# design.net
KiCad netlist of a schematic drawn in Altium Designer
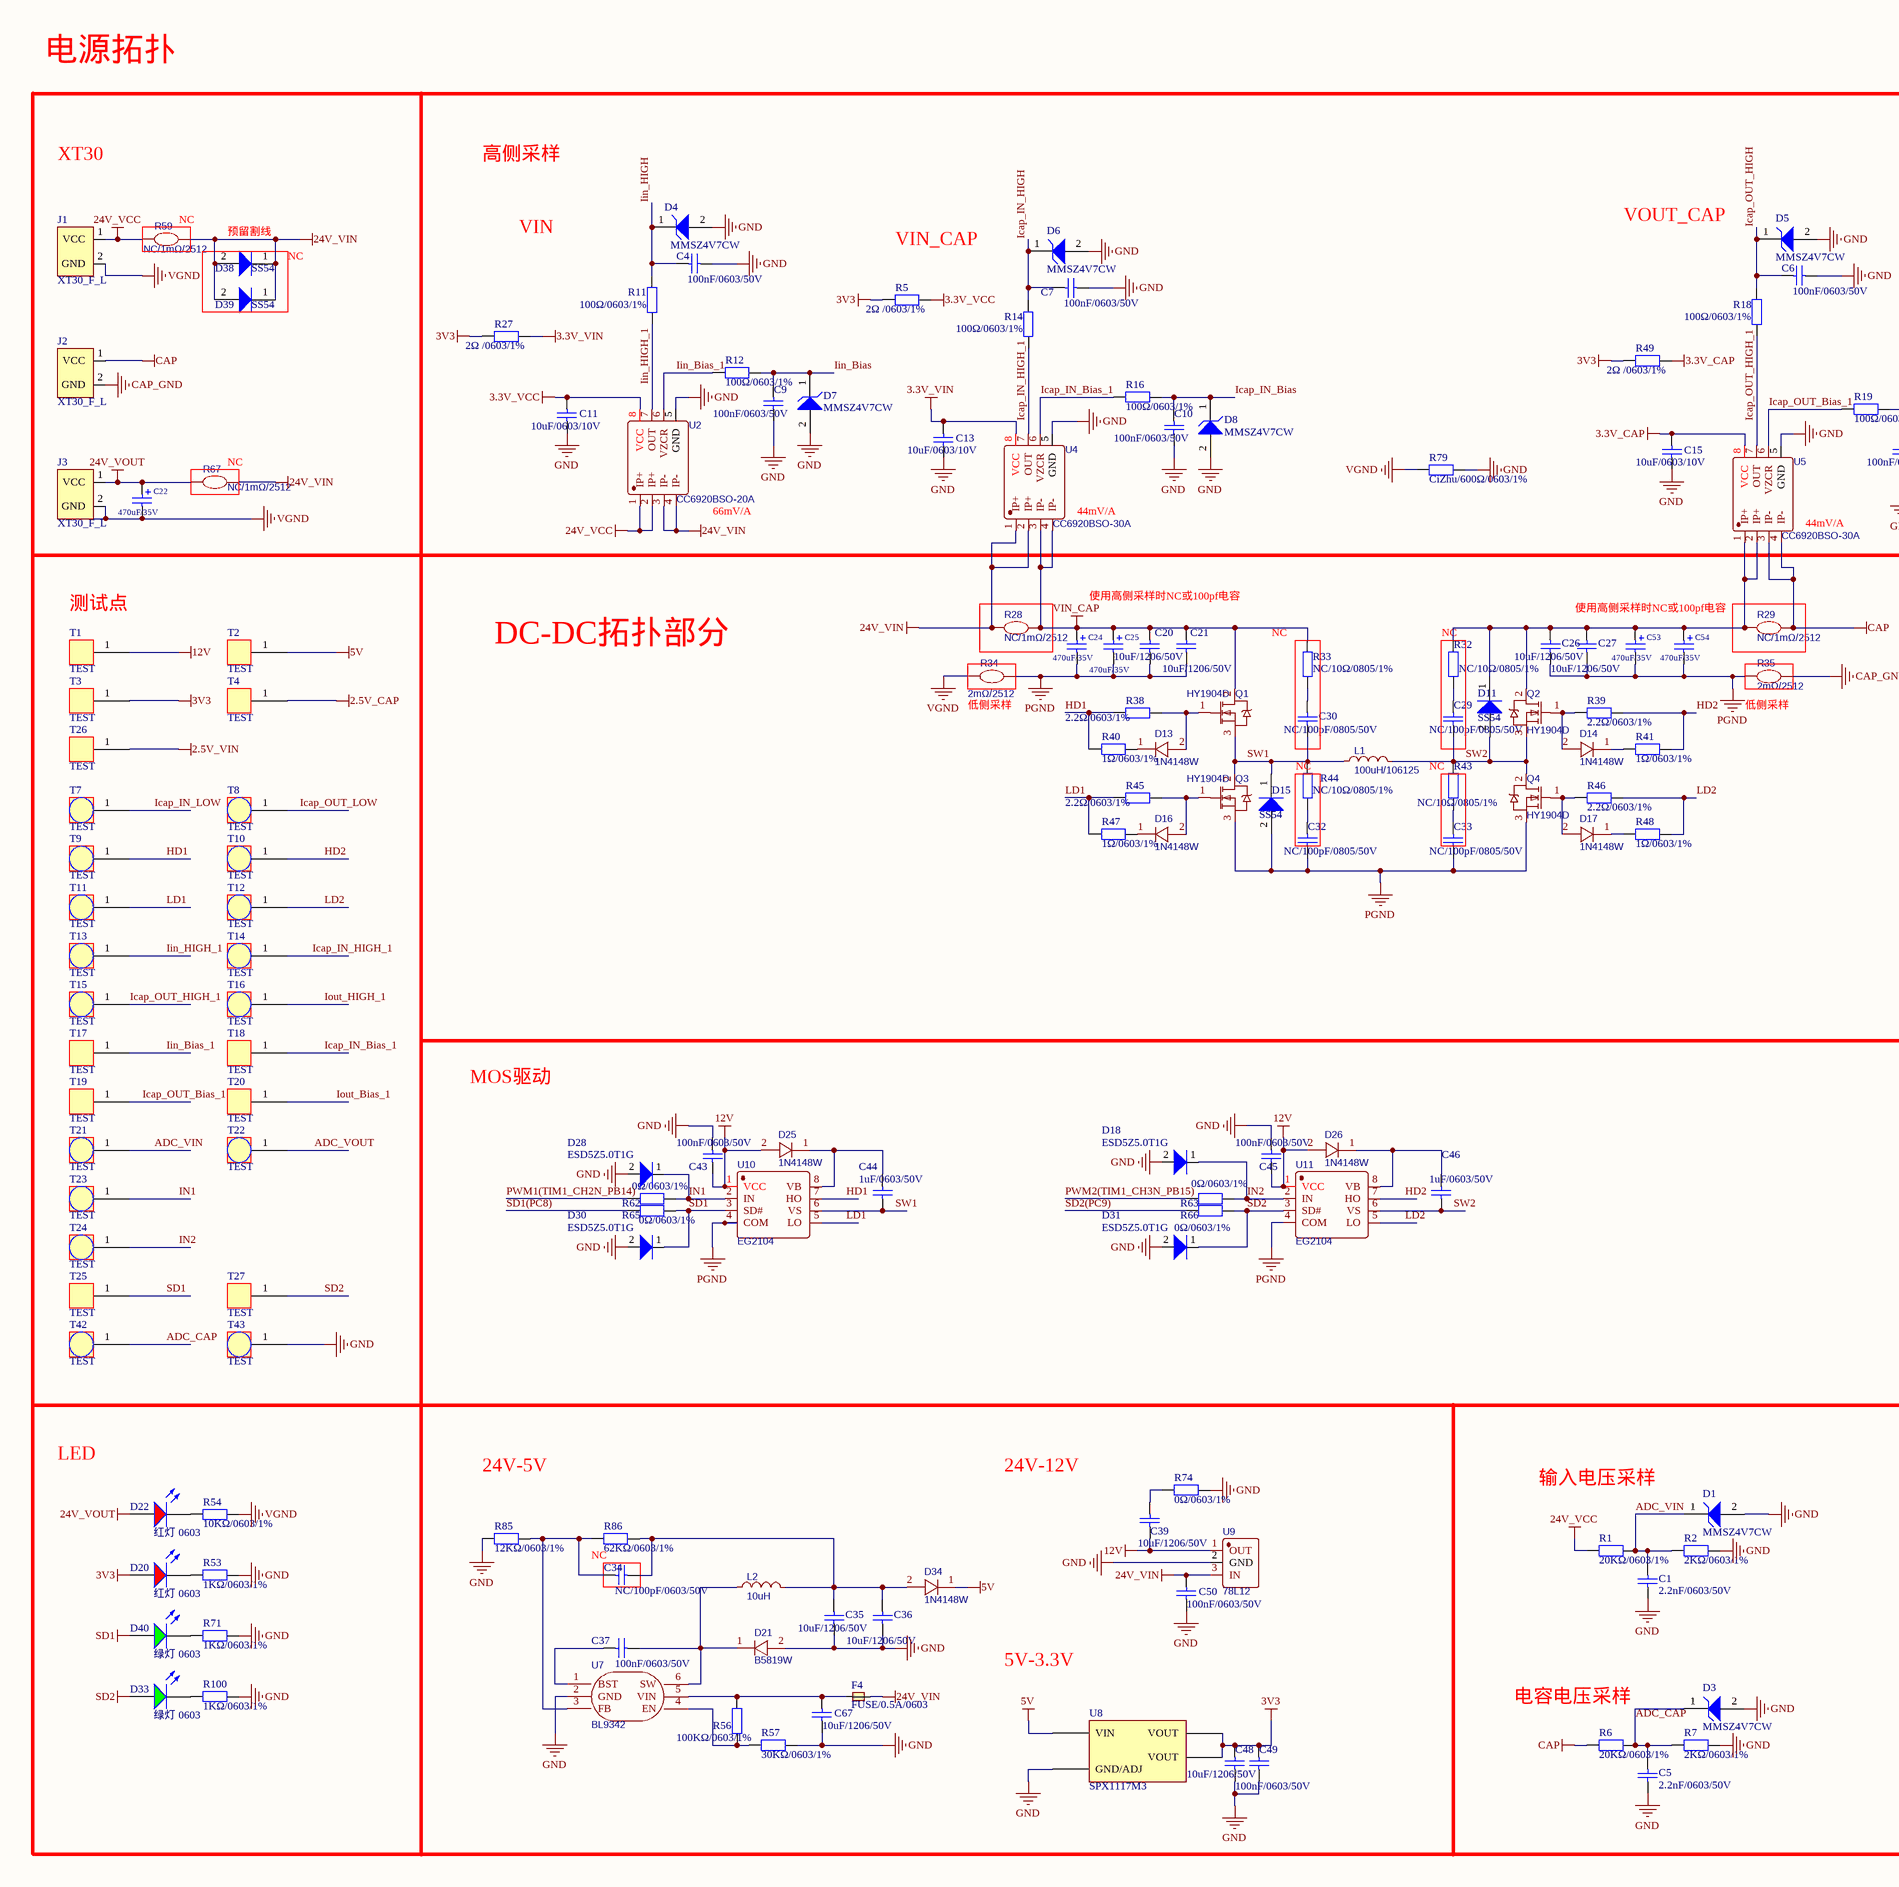
[diagram p0: 电源拓扑.SchDoc, left]
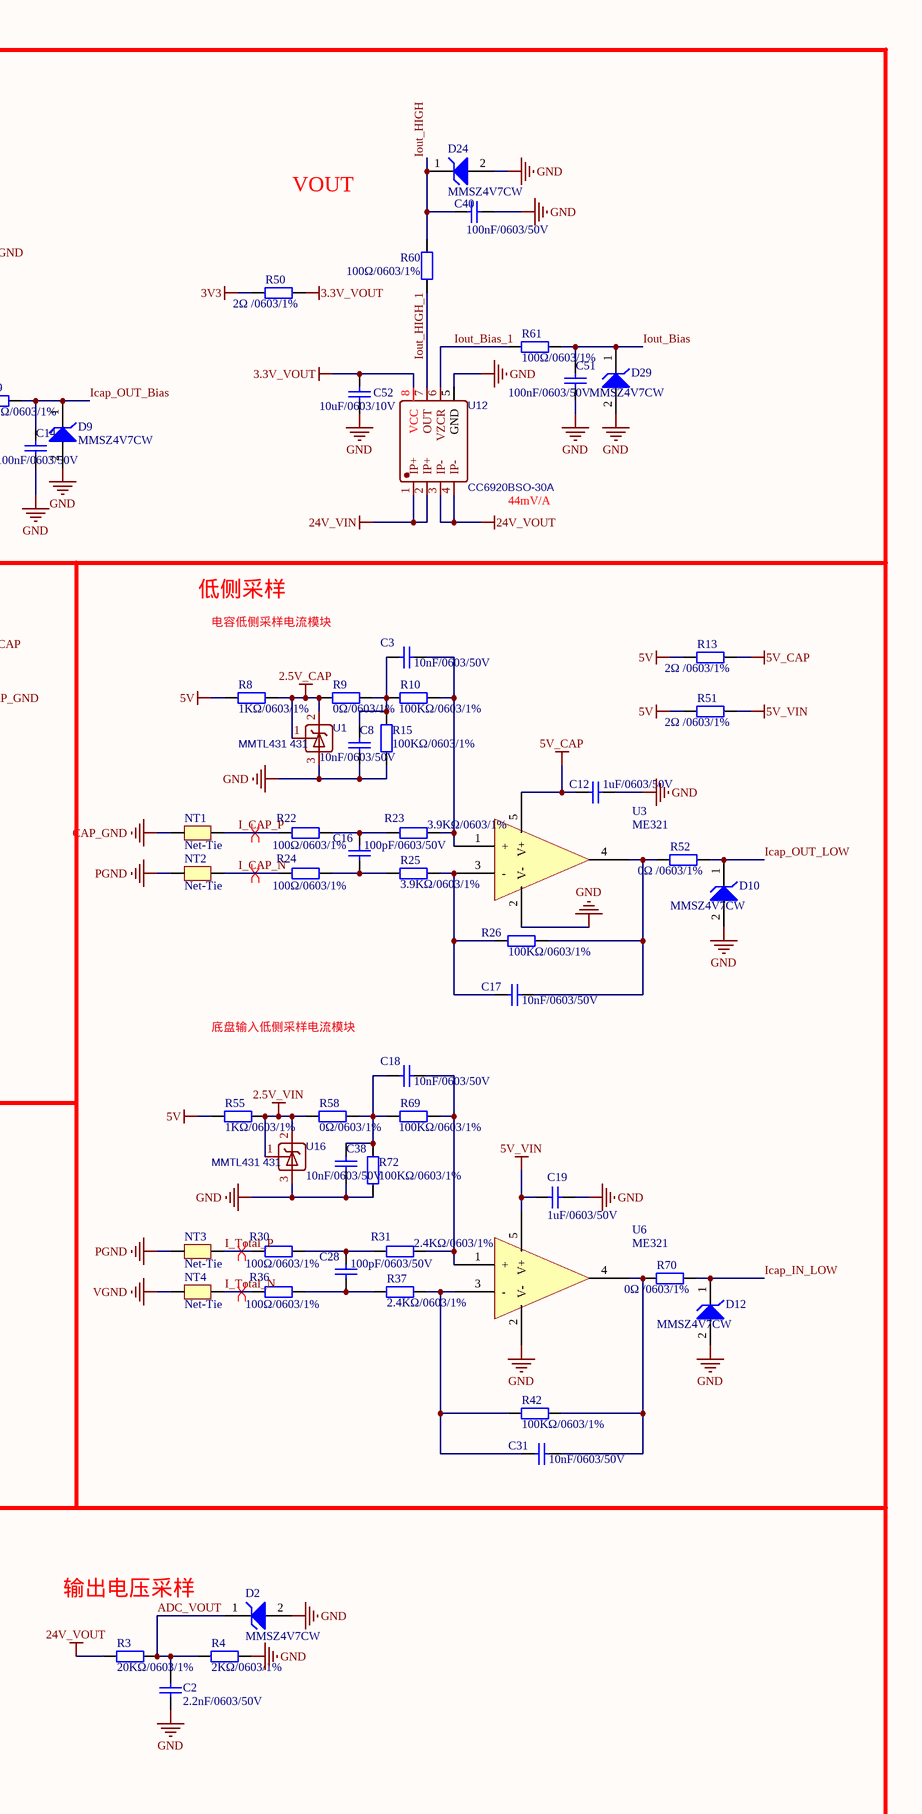
[diagram p1: 电源拓扑.SchDoc, right]

(export (version "E")
  (design (tool "Eeschema 10.0.6"))
  (components
    (comp (ref "C1")
      (value "2.2nF/0603/50V")
      (footprint "0603_C")
      (description "贴片电容")
      (libsource (lib "Miscellaneous Devices LC") (part "0603 100pF (101) 5% 50V"))
    )
    (comp (ref "C2")
      (value "2.2nF/0603/50V")
      (footprint "0603_C")
      (description "贴片电容")
      (libsource (lib "Miscellaneous Devices LC") (part "0603 100pF (101) 5% 50V"))
    )
    (comp (ref "C3")
      (value "10nF/0603/50V")
      (footprint "0603_C")
      (description "贴片电容")
      (libsource (lib "Miscellaneous Devices LC") (part "0603 100pF (101) 5% 50V"))
    )
    (comp (ref "C4")
      (value "100nF/0603/50V")
      (footprint "0603_C")
      (description "贴片电容")
      (libsource (lib "Miscellaneous Devices LC") (part "0603 100pF (101) 5% 50V"))
    )
    (comp (ref "C5")
      (value "2.2nF/0603/50V")
      (footprint "0603_C")
      (description "贴片电容")
      (libsource (lib "Miscellaneous Devices LC") (part "0603 100pF (101) 5% 50V"))
    )
    (comp (ref "C6")
      (value "100nF/0603/50V")
      (footprint "0603_C")
      (description "贴片电容")
      (libsource (lib "Miscellaneous Devices LC") (part "0603 100pF (101) 5% 50V"))
    )
    (comp (ref "C7")
      (value "100nF/0603/50V")
      (footprint "0603_C")
      (description "贴片电容")
      (libsource (lib "Miscellaneous Devices LC") (part "0603 100pF (101) 5% 50V"))
    )
    (comp (ref "C8")
      (value "10nF/0603/50V")
      (footprint "0603_C")
      (description "贴片电容")
      (libsource (lib "Miscellaneous Devices LC") (part "0603 100pF (101) 5% 50V"))
    )
    (comp (ref "C9")
      (value "100nF/0603/50V")
      (footprint "0603_C")
      (description "贴片电容")
      (libsource (lib "Miscellaneous Devices LC") (part "0603 100pF (101) 5% 50V"))
    )
    (comp (ref "C10")
      (value "100nF/0603/50V")
      (footprint "0603_C")
      (description "贴片电容")
      (libsource (lib "Miscellaneous Devices LC") (part "0603 100pF (101) 5% 50V"))
    )
    (comp (ref "C11")
      (value "10uF/0603/10V")
      (footprint "0603_C")
      (description "贴片电容")
      (libsource (lib "Miscellaneous Devices LC") (part "0603 10uF (106) 10% 10V"))
    )
    (comp (ref "C12")
      (value "1uF/0603/50V")
      (footprint "0603_C")
      (description "贴片电容")
      (libsource (lib "Miscellaneous Devices LC") (part "0603 100pF (101) 5% 50V"))
    )
    (comp (ref "C13")
      (value "10uF/0603/10V")
      (footprint "0603_C")
      (description "贴片电容")
      (libsource (lib "Miscellaneous Devices LC") (part "0603 10uF (106) 10% 10V"))
    )
    (comp (ref "C14")
      (value "100nF/0603/50V")
      (footprint "0603_C")
      (description "贴片电容")
      (libsource (lib "Miscellaneous Devices LC") (part "0603 100pF (101) 5% 50V"))
    )
    (comp (ref "C15")
      (value "10uF/0603/10V")
      (footprint "0603_C")
      (description "贴片电容")
      (libsource (lib "Miscellaneous Devices LC") (part "0603 10uF (106) 10% 10V"))
    )
    (comp (ref "C16")
      (value "100pF/0603/50V")
      (footprint "0603_C")
      (description "贴片电容")
      (libsource (lib "Miscellaneous Devices LC") (part "0603 100pF (101) 5% 50V"))
    )
    (comp (ref "C17")
      (value "10nF/0603/50V")
      (footprint "0603_C")
      (description "贴片电容")
      (libsource (lib "Miscellaneous Devices LC") (part "0603 100pF (101) 5% 50V"))
    )
    (comp (ref "C18")
      (value "10nF/0603/50V")
      (footprint "0603_C")
      (description "贴片电容")
      (libsource (lib "Miscellaneous Devices LC") (part "0603 100pF (101) 5% 50V"))
    )
    (comp (ref "C19")
      (value "1uF/0603/50V")
      (footprint "0603_C")
      (description "贴片电容")
      (libsource (lib "Miscellaneous Devices LC") (part "0603 10uF (106) 10% 10V"))
    )
    (comp (ref "C20")
      (value "10uF/1206/50V")
      (footprint "1206_C")
      (description "贴片电容")
      (libsource (lib "Miscellaneous Devices LC") (part "1206 10uF (106) 10% 50V"))
    )
    (comp (ref "C21")
      (value "10uF/1206/50V")
      (footprint "1206_C")
      (description "贴片电容")
      (libsource (lib "Miscellaneous Devices LC") (part "1206 10uF (106) 10% 50V"))
    )
    (comp (ref "C22")
      (value "470uF/35V")
      (footprint "CAP_10x16mm")
      (description "铝电解电容")
      (libsource (lib "数字电源") (part "CAP_470uF/35V/10x16mm"))
    )
    (comp (ref "C24")
      (value "470uF/35V")
      (footprint "CAP_10x16mm")
      (description "铝电解电容")
      (libsource (lib "数字电源") (part "CAP_470uF/35V/10x16mm"))
    )
    (comp (ref "C25")
      (value "470uF/35V")
      (footprint "CAP_10x16mm")
      (description "铝电解电容")
      (libsource (lib "数字电源") (part "CAP_470uF/35V/10x16mm"))
    )
    (comp (ref "C26")
      (value "10uF/1206/50V")
      (footprint "1206_C")
      (description "贴片电容")
      (libsource (lib "Miscellaneous Devices LC") (part "1206 10uF (106) 10% 50V"))
    )
    (comp (ref "C27")
      (value "10uF/1206/50V")
      (footprint "1206_C")
      (description "贴片电容")
      (libsource (lib "Miscellaneous Devices LC") (part "1206 10uF (106) 10% 50V"))
    )
    (comp (ref "C28")
      (value "100pF/0603/50V")
      (footprint "0603_C")
      (description "贴片电容")
      (libsource (lib "Miscellaneous Devices LC") (part "0603 100pF (101) 5% 50V"))
    )
    (comp (ref "C29")
      (value "NC/100pF/0805/50V")
      (footprint "0805_C")
      (description "贴片电容")
      (libsource (lib "Miscellaneous Devices LC") (part "0805 100pF (101) 5% 50V"))
    )
    (comp (ref "C30")
      (value "NC/100pF/0805/50V")
      (footprint "0805_C")
      (description "贴片电容")
      (libsource (lib "Miscellaneous Devices LC") (part "0805 100pF (101) 5% 50V"))
    )
    (comp (ref "C31")
      (value "10nF/0603/50V")
      (footprint "0603_C")
      (description "贴片电容")
      (libsource (lib "Miscellaneous Devices LC") (part "0603 100pF (101) 5% 50V"))
    )
    (comp (ref "C32")
      (value "NC/100pF/0805/50V")
      (footprint "0805_C")
      (description "贴片电容")
      (libsource (lib "Miscellaneous Devices LC") (part "0805 100pF (101) 5% 50V"))
    )
    (comp (ref "C33")
      (value "NC/100pF/0805/50V")
      (footprint "0805_C")
      (description "贴片电容")
      (libsource (lib "Miscellaneous Devices LC") (part "0805 100pF (101) 5% 50V"))
    )
    (comp (ref "C34")
      (value "NC/100pF/0603/50V")
      (footprint "0603_C")
      (description "贴片电容")
      (libsource (lib "Miscellaneous Devices LC") (part "0603 100pF (101) 5% 50V"))
    )
    (comp (ref "C35")
      (value "10uF/1206/50V")
      (footprint "1206_C")
      (description "贴片电容")
      (libsource (lib "Miscellaneous Devices LC") (part "1206 10uF (106) 10% 50V"))
    )
    (comp (ref "C36")
      (value "10uF/1206/50V")
      (footprint "1206_C")
      (description "贴片电容")
      (libsource (lib "Miscellaneous Devices LC") (part "1206 10uF (106) 10% 50V"))
    )
    (comp (ref "C37")
      (value "100nF/0603/50V")
      (footprint "0603_C")
      (description "贴片电容")
      (libsource (lib "Miscellaneous Devices LC") (part "0603 100pF (101) 5% 50V"))
    )
    (comp (ref "C38")
      (value "10nF/0603/50V")
      (footprint "0603_C")
      (description "贴片电容")
      (libsource (lib "Miscellaneous Devices LC") (part "0603 100pF (101) 5% 50V"))
    )
    (comp (ref "C39")
      (value "10uF/1206/50V")
      (footprint "1206_C")
      (description "贴片电容")
      (libsource (lib "Miscellaneous Devices LC") (part "1206 10uF (106) 10% 50V"))
    )
    (comp (ref "C40")
      (value "100nF/0603/50V")
      (footprint "0603_C")
      (description "贴片电容")
      (libsource (lib "Miscellaneous Devices LC") (part "0603 100pF (101) 5% 50V"))
    )
    (comp (ref "C43")
      (value "100nF/0603/50V")
      (footprint "0603_C")
      (description "贴片电容")
      (libsource (lib "Miscellaneous Devices LC") (part "0603 100pF (101) 5% 50V"))
    )
    (comp (ref "C44")
      (value "1uF/0603/50V")
      (footprint "0603_C")
      (description "贴片电容")
      (libsource (lib "Miscellaneous Devices LC") (part "0603 100pF (101) 5% 50V"))
    )
    (comp (ref "C45")
      (value "100nF/0603/50V")
      (footprint "0603_C")
      (description "贴片电容")
      (libsource (lib "Miscellaneous Devices LC") (part "0603 100pF (101) 5% 50V"))
    )
    (comp (ref "C46")
      (value "1uF/0603/50V")
      (footprint "0603_C")
      (description "贴片电容")
      (libsource (lib "Miscellaneous Devices LC") (part "0603 100pF (101) 5% 50V"))
    )
    (comp (ref "C48")
      (value "100nF/0603/50V")
      (footprint "0603_C")
      (description "贴片电容")
      (libsource (lib "Miscellaneous Devices LC") (part "0603 100pF (101) 5% 50V"))
    )
    (comp (ref "C49")
      (value "10uF/1206/50V")
      (footprint "1206_C")
      (description "贴片电容")
      (libsource (lib "Miscellaneous Devices LC") (part "1206 10uF (106) 10% 50V"))
    )
    (comp (ref "C50")
      (value "100nF/0603/50V")
      (footprint "0603_C")
      (description "贴片电容")
      (libsource (lib "Miscellaneous Devices LC") (part "0603 100pF (101) 5% 50V"))
    )
    (comp (ref "C51")
      (value "100nF/0603/50V")
      (footprint "0603_C")
      (description "贴片电容")
      (libsource (lib "Miscellaneous Devices LC") (part "0603 100pF (101) 5% 50V"))
    )
    (comp (ref "C52")
      (value "10uF/0603/10V")
      (footprint "0603_C")
      (description "贴片电容")
      (libsource (lib "Miscellaneous Devices LC") (part "0603 10uF (106) 10% 10V"))
    )
    (comp (ref "C53")
      (value "470uF/35V")
      (footprint "CAP_10x16mm")
      (description "铝电解电容")
      (libsource (lib "数字电源") (part "CAP_470uF/35V/10x16mm"))
    )
    (comp (ref "C54")
      (value "470uF/35V")
      (footprint "CAP_10x16mm")
      (description "铝电解电容")
      (libsource (lib "数字电源") (part "CAP_470uF/35V/10x16mm"))
    )
    (comp (ref "C67")
      (value "10uF/1206/50V")
      (footprint "1206_C")
      (description "贴片电容")
      (libsource (lib "Miscellaneous Devices LC") (part "1206 10uF (106) 10% 50V"))
    )
    (comp (ref "D1")
      (value "MMSZ4V7CW")
      (footprint "SOD-123")
      (description "稳压二极管")
      (libsource (lib "数字电源") (part "LL-34 ZMM3V3"))
    )
    (comp (ref "D2")
      (value "MMSZ4V7CW")
      (footprint "SOD-123")
      (description "稳压二极管")
      (libsource (lib "数字电源") (part "LL-34 ZMM3V3"))
    )
    (comp (ref "D3")
      (value "MMSZ4V7CW")
      (footprint "SOD-123")
      (description "稳压二极管")
      (libsource (lib "数字电源") (part "LL-34 ZMM3V3"))
    )
    (comp (ref "D4")
      (value "MMSZ4V7CW")
      (footprint "SOD-123")
      (description "稳压二极管")
      (libsource (lib "数字电源") (part "LL-34 ZMM3V3"))
    )
    (comp (ref "D5")
      (value "MMSZ4V7CW")
      (footprint "SOD-123")
      (description "稳压二极管")
      (libsource (lib "数字电源") (part "LL-34 ZMM3V3"))
    )
    (comp (ref "D6")
      (value "MMSZ4V7CW")
      (footprint "SOD-123")
      (description "稳压二极管")
      (libsource (lib "数字电源") (part "LL-34 ZMM3V3"))
    )
    (comp (ref "D7")
      (value "MMSZ4V7CW")
      (footprint "SOD-123")
      (description "稳压二极管")
      (libsource (lib "数字电源") (part "LL-34 ZMM3V3"))
    )
    (comp (ref "D8")
      (value "MMSZ4V7CW")
      (footprint "SOD-123")
      (description "稳压二极管")
      (libsource (lib "数字电源") (part "LL-34 ZMM3V3"))
    )
    (comp (ref "D9")
      (value "MMSZ4V7CW")
      (footprint "SOD-123")
      (description "稳压二极管")
      (libsource (lib "数字电源") (part "LL-34 ZMM3V3"))
    )
    (comp (ref "D10")
      (value "MMSZ4V7CW")
      (footprint "SOD-123")
      (description "稳压二极管")
      (libsource (lib "数字电源") (part "LL-34 ZMM3V3"))
    )
    (comp (ref "D11")
      (value "SS54")
      (footprint "SMA")
      (description "二极管")
      (libsource (lib "数字电源") (part "SS54"))
    )
    (comp (ref "D12")
      (value "MMSZ4V7CW")
      (footprint "SOD-123")
      (description "稳压二极管")
      (libsource (lib "数字电源") (part "LL-34 ZMM3V3"))
    )
    (comp (ref "D13")
      (value "1N4148W")
      (footprint "SOD-123_L2.7-W1.6-LS3.7-RD")
      (description "开关二极管")
      (fields (field (name "BOM_SUPPLIER PART") "C466653") (field (name "CONTRIBUTOR") "LCSC"))
      (libsource (lib "数字电源") (part "1N4148W"))
    )
    (comp (ref "D14")
      (value "1N4148W")
      (footprint "SOD-123_L2.7-W1.6-LS3.7-RD")
      (description "开关二极管")
      (fields (field (name "BOM_SUPPLIER PART") "C466653") (field (name "CONTRIBUTOR") "LCSC"))
      (libsource (lib "数字电源") (part "1N4148W"))
    )
    (comp (ref "D15")
      (value "SS54")
      (footprint "SMA")
      (description "二极管")
      (libsource (lib "数字电源") (part "SS54"))
    )
    (comp (ref "D16")
      (value "1N4148W")
      (footprint "SOD-123_L2.7-W1.6-LS3.7-RD")
      (description "开关二极管")
      (fields (field (name "BOM_SUPPLIER PART") "C466653") (field (name "CONTRIBUTOR") "LCSC"))
      (libsource (lib "数字电源") (part "1N4148W"))
    )
    (comp (ref "D17")
      (value "1N4148W")
      (footprint "SOD-123_L2.7-W1.6-LS3.7-RD")
      (description "开关二极管")
      (fields (field (name "BOM_SUPPLIER PART") "C466653") (field (name "CONTRIBUTOR") "LCSC"))
      (libsource (lib "数字电源") (part "1N4148W"))
    )
    (comp (ref "D18")
      (value "ESD5Z5.0T1G")
      (footprint "SOD-523")
      (description "单向TVS")
      (libsource (lib "数字电源") (part "TVS_SOD-523"))
    )
    (comp (ref "D20")
      (value "红灯 0603")
      (footprint "0603_LED_S1")
      (description "发光二极管")
      (libsource (lib "Miscellaneous Devices LC") (part "0603 红灯"))
    )
    (comp (ref "D21")
      (value "B5819W")
      (footprint "SOD-123_L2.7-W1.6-LS3.7-RD")
      (description "开关二极管")
      (fields
        (field (name "BOM_SUPPLIER PART") "C466653")
        (field (name "BOM_MANUFACTURER PART") "1N4148W")
        (field (name "CONTRIBUTOR") "LCSC")
      )
      (libsource (lib "数字电源") (part "1N4148W"))
    )
    (comp (ref "D22")
      (value "红灯 0603")
      (footprint "0603_LED_S1")
      (description "发光二极管")
      (libsource (lib "Miscellaneous Devices LC") (part "0603 红灯"))
    )
    (comp (ref "D24")
      (value "MMSZ4V7CW")
      (footprint "SOD-123")
      (description "稳压二极管")
      (libsource (lib "数字电源") (part "LL-34 ZMM3V3"))
    )
    (comp (ref "D25")
      (value "1N4148W")
      (footprint "SOD-123_L2.7-W1.6-LS3.7-RD")
      (description "开关二极管")
      (fields (field (name "BOM_SUPPLIER PART") "C466653") (field (name "CONTRIBUTOR") "LCSC"))
      (libsource (lib "数字电源") (part "1N4148W"))
    )
    (comp (ref "D26")
      (value "1N4148W")
      (footprint "SOD-123_L2.7-W1.6-LS3.7-RD")
      (description "开关二极管")
      (fields (field (name "BOM_SUPPLIER PART") "C466653") (field (name "CONTRIBUTOR") "LCSC"))
      (libsource (lib "数字电源") (part "1N4148W"))
    )
    (comp (ref "D28")
      (value "ESD5Z5.0T1G")
      (footprint "SOD-523")
      (description "单向TVS")
      (libsource (lib "数字电源") (part "TVS_SOD-523"))
    )
    (comp (ref "D29")
      (value "MMSZ4V7CW")
      (footprint "SOD-123")
      (description "稳压二极管")
      (libsource (lib "数字电源") (part "LL-34 ZMM3V3"))
    )
    (comp (ref "D30")
      (value "ESD5Z5.0T1G")
      (footprint "SOD-523")
      (description "单向TVS")
      (libsource (lib "数字电源") (part "TVS_SOD-523"))
    )
    (comp (ref "D31")
      (value "ESD5Z5.0T1G")
      (footprint "SOD-523")
      (description "单向TVS")
      (libsource (lib "数字电源") (part "TVS_SOD-523"))
    )
    (comp (ref "D33")
      (value "绿灯 0603")
      (footprint "0603_LED_S1")
      (description "发光二极管")
      (libsource (lib "Miscellaneous Devices LC") (part "0603 绿灯"))
    )
    (comp (ref "D34")
      (value "1N4148W")
      (footprint "SOD-123_L2.7-W1.6-LS3.7-RD")
      (description "开关二极管")
      (fields (field (name "BOM_SUPPLIER PART") "C466653") (field (name "CONTRIBUTOR") "LCSC"))
      (libsource (lib "数字电源") (part "1N4148W"))
    )
    (comp (ref "D38")
      (value "SS54")
      (footprint "SMA")
      (description "二极管")
      (libsource (lib "数字电源") (part "SS54"))
    )
    (comp (ref "D39")
      (value "SS54")
      (footprint "SMA")
      (description "二极管")
      (libsource (lib "数字电源") (part "SS54"))
    )
    (comp (ref "D40")
      (value "绿灯 0603")
      (footprint "0603_LED_S1")
      (description "发光二极管")
      (libsource (lib "Miscellaneous Devices LC") (part "0603 绿灯"))
    )
    (comp (ref "F4")
      (value "FUSE/0.5A/0603")
      (footprint "0.5A/0603")
      (description "FUSE")
      (libsource (lib "数字电源") (part "FUSE/0.5A/0603"))
    )
    (comp (ref "J1")
      (value "XT30_F_L")
      (footprint "RobotLab_Common_Used:XT30内嵌无极性标识_F")
      (description "卧式XT30")
      (libsource (lib "RobotLab_Common_Used") (part "XT30_F_L"))
    )
    (comp (ref "J2")
      (value "XT30_F_L")
      (footprint "RobotLab_Common_Used:XT30内嵌无极性标识_F")
      (description "卧式XT30")
      (libsource (lib "RobotLab_Common_Used") (part "XT30_F_L"))
    )
    (comp (ref "J3")
      (value "XT30_F_L")
      (footprint "RobotLab_Common_Used:XT30内嵌无极性标识_F")
      (description "卧式XT30")
      (libsource (lib "RobotLab_Common_Used") (part "XT30_F_L"))
    )
    (comp (ref "L1")
      (value "100uH/106125")
      (footprint "106125")
      (description "磁环电感")
      (fields
        (field (name "BOM_SUPPLIER PART") "C497913")
        (field (name "BOM_MANUFACTURER PART") "YSPI1365-470M")
        (field (name "CONTRIBUTOR") "LCSC")
      )
      (libsource (lib "数字电源") (part "106125 卧式"))
    )
    (comp (ref "L2")
      (value "10uH")
      (footprint "IND-SMD_L5.0-W5.0-1")
      (description "功率电感")
      (fields
        (field (name "BOM_SUPPLIER PART") "C497913")
        (field (name "BOM_MANUFACTURER PART") "YSPI1365-470M")
        (field (name "CONTRIBUTOR") "LCSC")
      )
      (libsource (lib "数字电源") (part "15uH"))
    )
    (comp (ref "NT1") (value "Net-Tie") (footprint "Net_Tie_10mil") (libsource (lib "数字电源") (part "Net-Tie")))
    (comp (ref "NT2") (value "Net-Tie") (footprint "Net_Tie_10mil") (libsource (lib "数字电源") (part "Net-Tie")))
    (comp (ref "NT3") (value "Net-Tie") (footprint "Net_Tie_10mil") (libsource (lib "数字电源") (part "Net-Tie")))
    (comp (ref "NT4") (value "Net-Tie") (footprint "Net_Tie_10mil") (libsource (lib "数字电源") (part "Net-Tie")))
    (comp (ref "Q1")
      (value "HY1904D")
      (footprint "TO-252-2_L6.6-W6.1-P4.57-LS9.9-TL-CW")
      (fields (field (name "BOM_SUPPLIER PART") "C122488"))
      (libsource (lib "数字电源") (part "HY1904D"))
    )
    (comp (ref "Q2")
      (value "HY1904D")
      (footprint "TO-252-2_L6.6-W6.1-P4.57-LS9.9-TL-CW")
      (fields (field (name "BOM_SUPPLIER PART") "C122488"))
      (libsource (lib "数字电源") (part "HY1904D"))
    )
    (comp (ref "Q3")
      (value "HY1904D")
      (footprint "TO-252-2_L6.6-W6.1-P4.57-LS9.9-TL-CW")
      (fields (field (name "BOM_SUPPLIER PART") "C122488"))
      (libsource (lib "数字电源") (part "HY1904D"))
    )
    (comp (ref "Q4")
      (value "HY1904D")
      (footprint "TO-252-2_L6.6-W6.1-P4.57-LS9.9-TL-CW")
      (fields (field (name "BOM_SUPPLIER PART") "C122488"))
      (libsource (lib "数字电源") (part "HY1904D"))
    )
    (comp (ref "R1")
      (value "20KΩ/0603/1%")
      (footprint "0603_R")
      (description "贴片电阻")
      (libsource (lib "Miscellaneous Devices LC") (part "0603 10KΩ (1002) 1%"))
    )
    (comp (ref "R2")
      (value "2KΩ/0603/1%")
      (footprint "0603_R")
      (description "贴片电阻")
      (libsource (lib "Miscellaneous Devices LC") (part "0603 10KΩ (1002) 1%"))
    )
    (comp (ref "R3")
      (value "20KΩ/0603/1%")
      (footprint "0603_R")
      (description "贴片电阻")
      (libsource (lib "Miscellaneous Devices LC") (part "0603 10KΩ (1002) 1%"))
    )
    (comp (ref "R4")
      (value "2KΩ/0603/1%")
      (footprint "0603_R")
      (description "贴片电阻")
      (libsource (lib "Miscellaneous Devices LC") (part "0603 10KΩ (1002) 1%"))
    )
    (comp (ref "R5")
      (value "2Ω /0603/1%")
      (footprint "0603_R")
      (description "贴片电阻")
      (libsource (lib "Miscellaneous Devices LC") (part "0603 2.2Ω (2R20) 1%"))
    )
    (comp (ref "R6")
      (value "20KΩ/0603/1%")
      (footprint "0603_R")
      (description "贴片电阻")
      (libsource (lib "Miscellaneous Devices LC") (part "0603 10KΩ (1002) 1%"))
    )
    (comp (ref "R7")
      (value "2KΩ/0603/1%")
      (footprint "0603_R")
      (description "贴片电阻")
      (libsource (lib "Miscellaneous Devices LC") (part "0603 10KΩ (1002) 1%"))
    )
    (comp (ref "R8")
      (value "1KΩ/0603/1%")
      (footprint "0603_R")
      (description "贴片电阻")
      (libsource (lib "Miscellaneous Devices LC") (part "0603 10KΩ (1002) 1%"))
    )
    (comp (ref "R9")
      (value "0Ω/0603/1%")
      (footprint "0603_R")
      (description "贴片电阻")
      (libsource (lib "Miscellaneous Devices LC") (part "0603 0Ω (0R0) 1%"))
    )
    (comp (ref "R10")
      (value "100KΩ/0603/1%")
      (footprint "0603_R")
      (description "贴片电阻")
      (libsource (lib "Miscellaneous Devices LC") (part "0603 10KΩ (1002) 1%"))
    )
    (comp (ref "R11")
      (value "100Ω/0603/1%")
      (footprint "0603_R")
      (description "贴片电阻")
      (libsource (lib "Miscellaneous Devices LC") (part "0603 100Ω (1000) 1%"))
    )
    (comp (ref "R12")
      (value "100Ω/0603/1%")
      (footprint "0603_R")
      (description "贴片电阻")
      (libsource (lib "") (part "0603 100Ω (1000) 1%_2"))
    )
    (comp (ref "R13")
      (value "2Ω /0603/1%")
      (footprint "0603_R")
      (description "贴片电阻")
      (libsource (lib "Miscellaneous Devices LC") (part "0603 2.2Ω (2R20) 1%"))
    )
    (comp (ref "R14")
      (value "100Ω/0603/1%")
      (footprint "0603_R")
      (description "贴片电阻")
      (libsource (lib "Miscellaneous Devices LC") (part "0603 100Ω (1000) 1%"))
    )
    (comp (ref "R15")
      (value "100KΩ/0603/1%")
      (footprint "0603_R")
      (description "贴片电阻")
      (libsource (lib "") (part "0603 10KΩ (1002) 1%_1"))
    )
    (comp (ref "R16")
      (value "100Ω/0603/1%")
      (footprint "0603_R")
      (description "贴片电阻")
      (libsource (lib "") (part "0603 100Ω (1000) 1%_2"))
    )
    (comp (ref "R18")
      (value "100Ω/0603/1%")
      (footprint "0603_R")
      (description "贴片电阻")
      (libsource (lib "Miscellaneous Devices LC") (part "0603 100Ω (1000) 1%"))
    )
    (comp (ref "R19")
      (value "100Ω/0603/1%")
      (footprint "0603_R")
      (description "贴片电阻")
      (libsource (lib "") (part "0603 100Ω (1000) 1%_2"))
    )
    (comp (ref "R22")
      (value "100Ω/0603/1%")
      (footprint "0603_R")
      (description "贴片电阻")
      (libsource (lib "") (part "0603 100Ω (1000) 1%_1"))
    )
    (comp (ref "R23")
      (value "3.9KΩ/0603/1%")
      (footprint "0603_R")
      (description "贴片电阻")
      (libsource (lib "Miscellaneous Devices LC") (part "0603 3.9KΩ (3901) 1%"))
    )
    (comp (ref "R24")
      (value "100Ω/0603/1%")
      (footprint "0603_R")
      (description "贴片电阻")
      (libsource (lib "") (part "0603 100Ω (1000) 1%_1"))
    )
    (comp (ref "R25")
      (value "3.9KΩ/0603/1%")
      (footprint "0603_R")
      (description "贴片电阻")
      (libsource (lib "Miscellaneous Devices LC") (part "0603 3.9KΩ (3901) 1%"))
    )
    (comp (ref "R26")
      (value "100KΩ/0603/1%")
      (footprint "0603_R")
      (description "贴片电阻")
      (libsource (lib "Miscellaneous Devices LC") (part "0603 200KΩ (2003) 1%"))
    )
    (comp (ref "R27")
      (value "2Ω /0603/1%")
      (footprint "0603_R")
      (description "贴片电阻")
      (libsource (lib "Miscellaneous Devices LC") (part "0603 2.2Ω (2R20) 1%"))
    )
    (comp (ref "R28")
      (value "NC/1mΩ/2512")
      (footprint "R2512")
      (description "2512采样")
      (fields
        (field (name "BOM_SUPPLIER PART") "C393070")
        (field (name "BOM_MANUFACTURER PART") "RLP25FEGR010")
        (field (name "CONTRIBUTOR") "LCSC")
      )
      (libsource (lib "数字电源") (part "0.01"))
    )
    (comp (ref "R29")
      (value "NC/1mΩ/2512")
      (footprint "R2512")
      (description "2512采样")
      (fields
        (field (name "BOM_SUPPLIER PART") "C393070")
        (field (name "BOM_MANUFACTURER PART") "RLP25FEGR010")
        (field (name "CONTRIBUTOR") "LCSC")
      )
      (libsource (lib "数字电源") (part "0.01"))
    )
    (comp (ref "R30")
      (value "100Ω/0603/1%")
      (footprint "0603_R")
      (description "贴片电阻")
      (libsource (lib "") (part "0603 100Ω (1000) 1%_1"))
    )
    (comp (ref "R31")
      (value "2.4KΩ/0603/1%")
      (footprint "0603_R")
      (description "贴片电阻")
      (libsource (lib "Miscellaneous Devices LC") (part "0603 3.9KΩ (3901) 1%"))
    )
    (comp (ref "R32")
      (value "NC/10Ω/0805/1%")
      (footprint "0805_R")
      (description "贴片电阻")
      (libsource (lib "Miscellaneous Devices LC") (part "0805 10Ω (10R0) 1%"))
    )
    (comp (ref "R33")
      (value "NC/10Ω/0805/1%")
      (footprint "0805_R")
      (description "贴片电阻")
      (libsource (lib "Miscellaneous Devices LC") (part "0805 10Ω (10R0) 1%"))
    )
    (comp (ref "R34")
      (value "2mΩ/2512")
      (footprint "R2512")
      (description "2512采样")
      (fields
        (field (name "BOM_SUPPLIER PART") "C393070")
        (field (name "BOM_MANUFACTURER PART") "RLP25FEGR010")
        (field (name "CONTRIBUTOR") "LCSC")
      )
      (libsource (lib "数字电源") (part "0.01"))
    )
    (comp (ref "R35")
      (value "2mΩ/2512")
      (footprint "R2512")
      (description "2512采样")
      (fields
        (field (name "BOM_SUPPLIER PART") "C393070")
        (field (name "BOM_MANUFACTURER PART") "RLP25FEGR010")
        (field (name "CONTRIBUTOR") "LCSC")
      )
      (libsource (lib "数字电源") (part "0.01"))
    )
    (comp (ref "R36")
      (value "100Ω/0603/1%")
      (footprint "0603_R")
      (description "贴片电阻")
      (libsource (lib "") (part "0603 100Ω (1000) 1%_1"))
    )
    (comp (ref "R37")
      (value "2.4KΩ/0603/1%")
      (footprint "0603_R")
      (description "贴片电阻")
      (libsource (lib "Miscellaneous Devices LC") (part "0603 3.9KΩ (3901) 1%"))
    )
    (comp (ref "R38")
      (value "2.2Ω/0603/1%")
      (footprint "0603_R")
      (description "贴片电阻")
      (libsource (lib "") (part "0603 0Ω (0R0) 1%_1"))
    )
    (comp (ref "R39")
      (value "2.2Ω/0603/1%")
      (footprint "0603_R")
      (description "贴片电阻")
      (libsource (lib "Miscellaneous Devices LC") (part "0603 0Ω (0R0) 1%"))
    )
    (comp (ref "R40")
      (value "1Ω/0603/1%")
      (footprint "0603_R")
      (description "贴片电阻")
      (libsource (lib "") (part "0603 0Ω (0R0) 1%_1"))
    )
    (comp (ref "R41")
      (value "1Ω/0603/1%")
      (footprint "0603_R")
      (description "贴片电阻")
      (libsource (lib "Miscellaneous Devices LC") (part "0603 0Ω (0R0) 1%"))
    )
    (comp (ref "R42")
      (value "100KΩ/0603/1%")
      (footprint "0603_R")
      (description "贴片电阻")
      (libsource (lib "Miscellaneous Devices LC") (part "0603 200KΩ (2003) 1%"))
    )
    (comp (ref "R43")
      (value "NC/10Ω/0805/1%")
      (footprint "0805_R")
      (description "贴片电阻")
      (libsource (lib "Miscellaneous Devices LC") (part "0805 10Ω (10R0) 1%"))
    )
    (comp (ref "R44")
      (value "NC/10Ω/0805/1%")
      (footprint "0805_R")
      (description "贴片电阻")
      (libsource (lib "Miscellaneous Devices LC") (part "0805 10Ω (10R0) 1%"))
    )
    (comp (ref "R45")
      (value "2.2Ω/0603/1%")
      (footprint "0603_R")
      (description "贴片电阻")
      (libsource (lib "") (part "0603 0Ω (0R0) 1%_1"))
    )
    (comp (ref "R46")
      (value "2.2Ω/0603/1%")
      (footprint "0603_R")
      (description "贴片电阻")
      (libsource (lib "Miscellaneous Devices LC") (part "0603 0Ω (0R0) 1%"))
    )
    (comp (ref "R47")
      (value "1Ω/0603/1%")
      (footprint "0603_R")
      (description "贴片电阻")
      (libsource (lib "") (part "0603 0Ω (0R0) 1%_1"))
    )
    (comp (ref "R48")
      (value "1Ω/0603/1%")
      (footprint "0603_R")
      (description "贴片电阻")
      (libsource (lib "Miscellaneous Devices LC") (part "0603 0Ω (0R0) 1%"))
    )
    (comp (ref "R49")
      (value "2Ω /0603/1%")
      (footprint "0603_R")
      (description "贴片电阻")
      (libsource (lib "Miscellaneous Devices LC") (part "0603 2.2Ω (2R20) 1%"))
    )
    (comp (ref "R50")
      (value "2Ω /0603/1%")
      (footprint "0603_R")
      (description "贴片电阻")
      (libsource (lib "Miscellaneous Devices LC") (part "0603 2.2Ω (2R20) 1%"))
    )
    (comp (ref "R51")
      (value "2Ω /0603/1%")
      (footprint "0603_R")
      (description "贴片电阻")
      (libsource (lib "Miscellaneous Devices LC") (part "0603 2.2Ω (2R20) 1%"))
    )
    (comp (ref "R52")
      (value "0Ω /0603/1%")
      (footprint "0603_R")
      (description "贴片电阻")
      (libsource (lib "Miscellaneous Devices LC") (part "0603 2.2Ω (2R20) 1%"))
    )
    (comp (ref "R53")
      (value "1KΩ/0603/1%")
      (footprint "0603_R")
      (description "贴片电阻")
      (libsource (lib "Miscellaneous Devices LC") (part "0603 10KΩ (1002) 1%"))
    )
    (comp (ref "R54")
      (value "10KΩ/0603/1%")
      (footprint "0603_R")
      (description "贴片电阻")
      (libsource (lib "Miscellaneous Devices LC") (part "0603 10KΩ (1002) 1%"))
    )
    (comp (ref "R55")
      (value "1KΩ/0603/1%")
      (footprint "0603_R")
      (description "贴片电阻")
      (libsource (lib "Miscellaneous Devices LC") (part "0603 10KΩ (1002) 1%"))
    )
    (comp (ref "R56")
      (value "100KΩ/0603/1%")
      (footprint "0603_R")
      (description "贴片电阻")
      (libsource (lib "Miscellaneous Devices LC") (part "0603 100KΩ (1003) 1%"))
    )
    (comp (ref "R57")
      (value "30KΩ/0603/1%")
      (footprint "0603_R")
      (description "贴片电阻")
      (libsource (lib "Miscellaneous Devices LC") (part "0603 30KΩ (3002) 1%"))
    )
    (comp (ref "R58")
      (value "0Ω/0603/1%")
      (footprint "0603_R")
      (description "贴片电阻")
      (libsource (lib "Miscellaneous Devices LC") (part "0603 0Ω (0R0) 1%"))
    )
    (comp (ref "R59")
      (value "NC/1mΩ/2512")
      (footprint "R2512")
      (description "2512采样")
      (fields
        (field (name "BOM_SUPPLIER PART") "C393070")
        (field (name "BOM_MANUFACTURER PART") "RLP25FEGR010")
        (field (name "CONTRIBUTOR") "LCSC")
      )
      (libsource (lib "数字电源") (part "0.01"))
    )
    (comp (ref "R60")
      (value "100Ω/0603/1%")
      (footprint "0603_R")
      (description "贴片电阻")
      (libsource (lib "Miscellaneous Devices LC") (part "0603 100Ω (1000) 1%"))
    )
    (comp (ref "R61")
      (value "100Ω/0603/1%")
      (footprint "0603_R")
      (description "贴片电阻")
      (libsource (lib "") (part "0603 100Ω (1000) 1%_2"))
    )
    (comp (ref "R62")
      (value "0Ω/0603/1%")
      (footprint "0603_R")
      (description "贴片电阻")
      (libsource (lib "Miscellaneous Devices LC") (part "0603 0Ω (0R0) 1%"))
    )
    (comp (ref "R63")
      (value "0Ω/0603/1%")
      (footprint "0603_R")
      (description "贴片电阻")
      (libsource (lib "Miscellaneous Devices LC") (part "0603 0Ω (0R0) 1%"))
    )
    (comp (ref "R65")
      (value "0Ω/0603/1%")
      (footprint "0603_R")
      (description "贴片电阻")
      (libsource (lib "Miscellaneous Devices LC") (part "0603 0Ω (0R0) 1%"))
    )
    (comp (ref "R66")
      (value "0Ω/0603/1%")
      (footprint "0603_R")
      (description "贴片电阻")
      (libsource (lib "Miscellaneous Devices LC") (part "0603 0Ω (0R0) 1%"))
    )
    (comp (ref "R67")
      (value "NC/1mΩ/2512")
      (footprint "R2512")
      (description "2512采样")
      (fields
        (field (name "BOM_SUPPLIER PART") "C393070")
        (field (name "BOM_MANUFACTURER PART") "RLP25FEGR010")
        (field (name "CONTRIBUTOR") "LCSC")
      )
      (libsource (lib "数字电源") (part "0.01"))
    )
    (comp (ref "R69")
      (value "100KΩ/0603/1%")
      (footprint "0603_R")
      (description "贴片电阻")
      (libsource (lib "Miscellaneous Devices LC") (part "0603 10KΩ (1002) 1%"))
    )
    (comp (ref "R70")
      (value "0Ω /0603/1%")
      (footprint "0603_R")
      (description "贴片电阻")
      (libsource (lib "Miscellaneous Devices LC") (part "0603 2.2Ω (2R20) 1%"))
    )
    (comp (ref "R71")
      (value "1KΩ/0603/1%")
      (footprint "0603_R")
      (description "贴片电阻")
      (libsource (lib "Miscellaneous Devices LC") (part "0603 10KΩ (1002) 1%"))
    )
    (comp (ref "R72")
      (value "100KΩ/0603/1%")
      (footprint "0603_R")
      (description "贴片电阻")
      (libsource (lib "") (part "0603 10KΩ (1002) 1%_1"))
    )
    (comp (ref "R74")
      (value "0Ω/0603/1%")
      (footprint "0603_R")
      (description "贴片电阻")
      (libsource (lib "Miscellaneous Devices LC") (part "0603 0Ω (0R0) 1%"))
    )
    (comp (ref "R79")
      (value "CiZhu/600Ω/0603/1%")
      (footprint "0603_R")
      (description "贴片电阻")
      (libsource (lib "Miscellaneous Devices LC") (part "0603 0Ω (0R0) 1%"))
    )
    (comp (ref "R85")
      (value "12KΩ/0603/1%")
      (footprint "0603_R")
      (description "贴片电阻")
      (libsource (lib "Miscellaneous Devices LC") (part "0603 12KΩ (1202) 1%"))
    )
    (comp (ref "R86")
      (value "62KΩ/0603/1%")
      (footprint "0603_R")
      (description "贴片电阻")
      (libsource (lib "Miscellaneous Devices LC") (part "0603 62KΩ (6202) 1%"))
    )
    (comp (ref "R100")
      (value "1KΩ/0603/1%")
      (footprint "0603_R")
      (description "贴片电阻")
      (libsource (lib "Miscellaneous Devices LC") (part "0603 10KΩ (1002) 1%"))
    )
    (comp (ref "T1")
      (value "TEST")
      (footprint "测试点")
      (description "测试点")
      (libsource (lib "数字电源") (part "测试点"))
    )
    (comp (ref "T2")
      (value "TEST")
      (footprint "测试点")
      (description "测试点")
      (libsource (lib "数字电源") (part "测试点"))
    )
    (comp (ref "T3")
      (value "TEST")
      (footprint "测试点")
      (description "测试点")
      (libsource (lib "数字电源") (part "测试点"))
    )
    (comp (ref "T4")
      (value "TEST")
      (footprint "测试点")
      (description "测试点")
      (libsource (lib "数字电源") (part "测试点"))
    )
    (comp (ref "T7")
      (value "TEST")
      (footprint "TEST_hole")
      (description "测试孔")
      (libsource (lib "数字电源") (part "测试孔"))
    )
    (comp (ref "T8")
      (value "TEST")
      (footprint "TEST_hole")
      (description "测试孔")
      (libsource (lib "数字电源") (part "测试孔"))
    )
    (comp (ref "T9")
      (value "TEST")
      (footprint "TEST_hole")
      (description "测试孔")
      (libsource (lib "数字电源") (part "测试孔"))
    )
    (comp (ref "T10")
      (value "TEST")
      (footprint "TEST_hole")
      (description "测试孔")
      (libsource (lib "数字电源") (part "测试孔"))
    )
    (comp (ref "T11")
      (value "TEST")
      (footprint "TEST_hole")
      (description "测试孔")
      (libsource (lib "数字电源") (part "测试孔"))
    )
    (comp (ref "T12")
      (value "TEST")
      (footprint "TEST_hole")
      (description "测试孔")
      (libsource (lib "数字电源") (part "测试孔"))
    )
    (comp (ref "T13")
      (value "TEST")
      (footprint "TEST_hole")
      (description "测试孔")
      (libsource (lib "数字电源") (part "测试孔"))
    )
    (comp (ref "T14")
      (value "TEST")
      (footprint "TEST_hole")
      (description "测试孔")
      (libsource (lib "数字电源") (part "测试孔"))
    )
    (comp (ref "T15")
      (value "TEST")
      (footprint "TEST_hole")
      (description "测试孔")
      (libsource (lib "数字电源") (part "测试孔"))
    )
    (comp (ref "T16")
      (value "TEST")
      (footprint "TEST_hole")
      (description "测试孔")
      (libsource (lib "数字电源") (part "测试孔"))
    )
    (comp (ref "T17")
      (value "TEST")
      (footprint "测试点")
      (description "测试点")
      (libsource (lib "数字电源") (part "测试点"))
    )
    (comp (ref "T18")
      (value "TEST")
      (footprint "测试点")
      (description "测试点")
      (libsource (lib "数字电源") (part "测试点"))
    )
    (comp (ref "T19")
      (value "TEST")
      (footprint "测试点")
      (description "测试点")
      (libsource (lib "数字电源") (part "测试点"))
    )
    (comp (ref "T20")
      (value "TEST")
      (footprint "测试点")
      (description "测试点")
      (libsource (lib "数字电源") (part "测试点"))
    )
    (comp (ref "T21")
      (value "TEST")
      (footprint "TEST_hole")
      (description "测试孔")
      (libsource (lib "数字电源") (part "测试孔"))
    )
    (comp (ref "T22")
      (value "TEST")
      (footprint "TEST_hole")
      (description "测试孔")
      (libsource (lib "数字电源") (part "测试孔"))
    )
    (comp (ref "T23")
      (value "TEST")
      (footprint "TEST_hole")
      (description "测试孔")
      (libsource (lib "数字电源") (part "测试孔"))
    )
    (comp (ref "T24")
      (value "TEST")
      (footprint "TEST_hole")
      (description "测试孔")
      (libsource (lib "数字电源") (part "测试孔"))
    )
    (comp (ref "T25")
      (value "TEST")
      (footprint "测试点")
      (description "测试点")
      (libsource (lib "数字电源") (part "测试点"))
    )
    (comp (ref "T26")
      (value "TEST")
      (footprint "测试点")
      (description "测试点")
      (libsource (lib "数字电源") (part "测试点"))
    )
    (comp (ref "T27")
      (value "TEST")
      (footprint "测试点")
      (description "测试点")
      (libsource (lib "数字电源") (part "测试点"))
    )
    (comp (ref "T42")
      (value "TEST")
      (footprint "TEST_hole")
      (description "测试孔")
      (libsource (lib "数字电源") (part "测试孔"))
    )
    (comp (ref "T43")
      (value "TEST")
      (footprint "TEST_hole")
      (description "测试孔")
      (libsource (lib "数字电源") (part "测试孔"))
    )
    (comp (ref "U1")
      (value "MMTL431 431")
      (footprint "SOT-23-3_L2.9-W1.6-P1.90-LS2.8-BR")
      (fields (field (name "BOM_SUPPLIER PART") "C2828456") (field (name "CONTRIBUTOR") "LCSC"))
      (libsource (lib "数字电源") (part "MMTL431 431"))
    )
    (comp (ref "U2")
      (value "CC6920BSO-20A")
      (footprint "SOP-8_L5.0-W4.0-P1.27-LS6.2-BL")
      (fields
        (field (name "BOM_SUPPLIER PART") "C2760489")
        (field (name "BOM_MANUFACTURER PART") "CC6920SO-20A")
        (field (name "CONTRIBUTOR") "LCSC")
      )
      (libsource (lib "数字电源") (part "CC6920SO-20A"))
    )
    (comp (ref "U3")
      (value "ME321")
      (footprint "SOT-23（ME321）")
      (description "轨对轨运放")
      (libsource (lib "数字电源") (part "ME321"))
    )
    (comp (ref "U4")
      (value "CC6920BSO-30A")
      (footprint "SOP-8_L5.0-W4.0-P1.27-LS6.2-BL")
      (fields
        (field (name "BOM_SUPPLIER PART") "C2760489")
        (field (name "BOM_MANUFACTURER PART") "CC6920SO-20A")
        (field (name "CONTRIBUTOR") "LCSC")
      )
      (libsource (lib "数字电源") (part "CC6920SO-20A"))
    )
    (comp (ref "U5")
      (value "CC6920BSO-30A")
      (footprint "SOP-8_L5.0-W4.0-P1.27-LS6.2-BL")
      (fields
        (field (name "BOM_SUPPLIER PART") "C2760489")
        (field (name "BOM_MANUFACTURER PART") "CC6920SO-20A")
        (field (name "CONTRIBUTOR") "LCSC")
      )
      (libsource (lib "数字电源") (part "CC6920SO-20A"))
    )
    (comp (ref "U6")
      (value "ME321")
      (footprint "SOT-23（ME321）")
      (description "轨对轨运放")
      (libsource (lib "数字电源") (part "ME321"))
    )
    (comp (ref "U7")
      (value "BL9342")
      (footprint "SOT-23-6_L2.9-W1.6-P0.95-LS2.8-BR")
      (fields (field (name "BOM_SUPPLIER PART") "C93176"))
      (libsource (lib "数字电源") (part "BL9342"))
    )
    (comp (ref "U8")
      (value "SPX1117M3")
      (footprint "SOT-223")
      (description "LDO SOT-223")
      (libsource (lib "数字电源") (part "ZLDO1117"))
    )
    (comp (ref "U9")
      (value "78L12")
      (footprint "SOT-89-3_L4.5-W2.5-P1.50-LS4.1-BL")
      (description "LDO")
      (fields
        (field (name "BOM_SUPPLIER PART") "C2898658")
        (field (name "BOM_MANUFACTURER PART") "78L05")
        (field (name "CONTRIBUTOR") "LCSC")
      )
      (libsource (lib "数字电源") (part "78L05_C2898658"))
    )
    (comp (ref "U10")
      (value "EG2104")
      (footprint "SOIC-8_L4.9-W3.9-P1.27-LS6.0-BL")
      (fields
        (field (name "BOM_MANUFACTURER PART") "IR2104STRPBF")
        (field (name "BOM_SUPPLIER PART") "C2960")
      )
      (libsource (lib "数字电源") (part "IR2104STRPBF"))
    )
    (comp (ref "U11")
      (value "EG2104")
      (footprint "SOIC-8_L4.9-W3.9-P1.27-LS6.0-BL")
      (fields
        (field (name "BOM_MANUFACTURER PART") "IR2104STRPBF")
        (field (name "BOM_SUPPLIER PART") "C2960")
      )
      (libsource (lib "数字电源") (part "IR2104STRPBF"))
    )
    (comp (ref "U12")
      (value "CC6920BSO-30A")
      (footprint "SOP-8_L5.0-W4.0-P1.27-LS6.2-BL")
      (fields
        (field (name "BOM_SUPPLIER PART") "C2760489")
        (field (name "BOM_MANUFACTURER PART") "CC6920SO-20A")
        (field (name "CONTRIBUTOR") "LCSC")
      )
      (libsource (lib "数字电源") (part "CC6920SO-20A"))
    )
    (comp (ref "U16")
      (value "MMTL431 431")
      (footprint "SOT-23-3_L2.9-W1.6-P1.90-LS2.8-BR")
      (fields (field (name "BOM_SUPPLIER PART") "C2828456") (field (name "CONTRIBUTOR") "LCSC"))
      (libsource (lib "数字电源") (part "MMTL431 431"))
    )
  )
  (nets
    (net (code "1") (name "/ADC_CAP") (class "Default")
      (node (ref "C5") (pin "2") (pinfunction "2_2") (pintype "passive"))
      (node (ref "D3") (pin "1") (pinfunction "K_1") (pintype "passive"))
      (node (ref "R6") (pin "1") (pinfunction "1_1") (pintype "passive"))
      (node (ref "R7") (pin "2") (pinfunction "2_2") (pintype "passive"))
      (node (ref "T42") (pin "1") (pinfunction "VIN_1") (pintype "passive"))
    )
    (net (code "2") (name "/ADC_VIN") (class "Default")
      (node (ref "C1") (pin "2") (pinfunction "2_2") (pintype "passive"))
      (node (ref "D1") (pin "1") (pinfunction "K_1") (pintype "passive"))
      (node (ref "R1") (pin "1") (pinfunction "1_1") (pintype "passive"))
      (node (ref "R2") (pin "2") (pinfunction "2_2") (pintype "passive"))
      (node (ref "T21") (pin "1") (pinfunction "VIN_1") (pintype "passive"))
    )
    (net (code "3") (name "/ADC_VOUT") (class "Default")
      (node (ref "C2") (pin "2") (pinfunction "2_2") (pintype "passive"))
      (node (ref "D2") (pin "1") (pinfunction "K_1") (pintype "passive"))
      (node (ref "R3") (pin "1") (pinfunction "1_1") (pintype "passive"))
      (node (ref "R4") (pin "2") (pinfunction "2_2") (pintype "passive"))
      (node (ref "T22") (pin "1") (pinfunction "VIN_1") (pintype "passive"))
    )
    (net (code "4") (name "/HD1") (class "Default")
      (node (ref "R38") (pin "1") (pinfunction "1_1") (pintype "passive"))
      (node (ref "R40") (pin "1") (pinfunction "1_1") (pintype "passive"))
      (node (ref "T9") (pin "1") (pinfunction "VIN_1") (pintype "passive"))
      (node (ref "U10") (pin "7") (pinfunction "HO_7") (pintype "passive"))
    )
    (net (code "5") (name "/HD2") (class "Default")
      (node (ref "R39") (pin "1") (pinfunction "1_1") (pintype "passive"))
      (node (ref "R41") (pin "1") (pinfunction "1_1") (pintype "passive"))
      (node (ref "T10") (pin "1") (pinfunction "VIN_1") (pintype "passive"))
      (node (ref "U11") (pin "7") (pinfunction "HO_7") (pintype "passive"))
    )
    (net (code "6") (name "/IN1") (class "Default")
      (node (ref "D28") (pin "1") (pinfunction "K_1") (pintype "passive"))
      (node (ref "R62") (pin "1") (pinfunction "1_1") (pintype "passive"))
      (node (ref "T23") (pin "1") (pinfunction "VIN_1") (pintype "passive"))
      (node (ref "U10") (pin "2") (pinfunction "IN_2") (pintype "passive"))
    )
    (net (code "7") (name "/IN2") (class "Default")
      (node (ref "D18") (pin "1") (pinfunction "K_1") (pintype "passive"))
      (node (ref "R63") (pin "1") (pinfunction "1_1") (pintype "passive"))
      (node (ref "T24") (pin "1") (pinfunction "VIN_1") (pintype "passive"))
      (node (ref "U11") (pin "2") (pinfunction "IN_2") (pintype "passive"))
    )
    (net (code "8") (name "/I_CAP_N") (class "Default")
      (node (ref "NT2") (pin "2") (pinfunction "2_2") (pintype "passive"))
      (node (ref "R24") (pin "1") (pinfunction "1_1") (pintype "passive"))
    )
    (net (code "9") (name "/I_CAP_P") (class "Default")
      (node (ref "NT1") (pin "2") (pinfunction "2_2") (pintype "passive"))
      (node (ref "R22") (pin "1") (pinfunction "1_1") (pintype "passive"))
    )
    (net (code "10") (name "/I_Total_N") (class "Default")
      (node (ref "NT4") (pin "2") (pinfunction "2_2") (pintype "passive"))
      (node (ref "R36") (pin "1") (pinfunction "1_1") (pintype "passive"))
    )
    (net (code "11") (name "/I_Total_P") (class "Default")
      (node (ref "NT3") (pin "2") (pinfunction "2_2") (pintype "passive"))
      (node (ref "R30") (pin "1") (pinfunction "1_1") (pintype "passive"))
    )
    (net (code "12") (name "/Icap_IN_Bias") (class "Default")
      (node (ref "C10") (pin "2") (pinfunction "2_2") (pintype "passive"))
      (node (ref "D8") (pin "1") (pinfunction "K_1") (pintype "passive"))
      (node (ref "R16") (pin "1") (pinfunction "1_1") (pintype "passive"))
    )
    (net (code "13") (name "/Icap_IN_Bias_1") (class "Default")
      (node (ref "R16") (pin "2") (pinfunction "2_2") (pintype "passive"))
      (node (ref "T18") (pin "1") (pinfunction "VIN_1") (pintype "passive"))
      (node (ref "U4") (pin "6") (pinfunction "VZCR_6") (pintype "passive"))
    )
    (net (code "14") (name "/Icap_IN_HIGH") (class "Default")
      (node (ref "C7") (pin "1") (pinfunction "1_1") (pintype "passive"))
      (node (ref "D6") (pin "1") (pinfunction "K_1") (pintype "passive"))
      (node (ref "R14") (pin "2") (pinfunction "2_2") (pintype "passive"))
    )
    (net (code "15") (name "/Icap_IN_HIGH_1") (class "Default")
      (node (ref "R14") (pin "1") (pinfunction "1_1") (pintype "passive"))
      (node (ref "T14") (pin "1") (pinfunction "VIN_1") (pintype "passive"))
      (node (ref "U4") (pin "7") (pinfunction "OUT_7") (pintype "passive"))
    )
    (net (code "16") (name "/Icap_IN_LOW") (class "Default")
      (node (ref "D12") (pin "1") (pinfunction "K_1") (pintype "passive"))
      (node (ref "R70") (pin "2") (pinfunction "2_2") (pintype "passive"))
      (node (ref "T7") (pin "1") (pinfunction "VIN_1") (pintype "passive"))
    )
    (net (code "17") (name "/Icap_OUT_Bias") (class "Default")
      (node (ref "C14") (pin "2") (pinfunction "2_2") (pintype "passive"))
      (node (ref "D9") (pin "1") (pinfunction "K_1") (pintype "passive"))
      (node (ref "R19") (pin "1") (pinfunction "1_1") (pintype "passive"))
    )
    (net (code "18") (name "/Icap_OUT_Bias_1") (class "Default")
      (node (ref "R19") (pin "2") (pinfunction "2_2") (pintype "passive"))
      (node (ref "T19") (pin "1") (pinfunction "VIN_1") (pintype "passive"))
      (node (ref "U5") (pin "6") (pinfunction "VZCR_6") (pintype "passive"))
    )
    (net (code "19") (name "/Icap_OUT_HIGH") (class "Default")
      (node (ref "C6") (pin "1") (pinfunction "1_1") (pintype "passive"))
      (node (ref "D5") (pin "1") (pinfunction "K_1") (pintype "passive"))
      (node (ref "R18") (pin "2") (pinfunction "2_2") (pintype "passive"))
    )
    (net (code "20") (name "/Icap_OUT_HIGH_1") (class "Default")
      (node (ref "R18") (pin "1") (pinfunction "1_1") (pintype "passive"))
      (node (ref "T15") (pin "1") (pinfunction "VIN_1") (pintype "passive"))
      (node (ref "U5") (pin "7") (pinfunction "OUT_7") (pintype "passive"))
    )
    (net (code "21") (name "/Icap_OUT_LOW") (class "Default")
      (node (ref "D10") (pin "1") (pinfunction "K_1") (pintype "passive"))
      (node (ref "R52") (pin "2") (pinfunction "2_2") (pintype "passive"))
      (node (ref "T8") (pin "1") (pinfunction "VIN_1") (pintype "passive"))
    )
    (net (code "22") (name "/Iin_Bias") (class "Default")
      (node (ref "C9") (pin "2") (pinfunction "2_2") (pintype "passive"))
      (node (ref "D7") (pin "1") (pinfunction "K_1") (pintype "passive"))
      (node (ref "R12") (pin "1") (pinfunction "1_1") (pintype "passive"))
    )
    (net (code "23") (name "/Iin_Bias_1") (class "Default")
      (node (ref "R12") (pin "2") (pinfunction "2_2") (pintype "passive"))
      (node (ref "T17") (pin "1") (pinfunction "VIN_1") (pintype "passive"))
      (node (ref "U2") (pin "6") (pinfunction "VZCR_6") (pintype "passive"))
    )
    (net (code "24") (name "/Iin_HIGH") (class "Default")
      (node (ref "C4") (pin "1") (pinfunction "1_1") (pintype "passive"))
      (node (ref "D4") (pin "1") (pinfunction "K_1") (pintype "passive"))
      (node (ref "R11") (pin "2") (pinfunction "2_2") (pintype "passive"))
    )
    (net (code "25") (name "/Iin_HIGH_1") (class "Default")
      (node (ref "R11") (pin "1") (pinfunction "1_1") (pintype "passive"))
      (node (ref "T13") (pin "1") (pinfunction "VIN_1") (pintype "passive"))
      (node (ref "U2") (pin "7") (pinfunction "OUT_7") (pintype "passive"))
    )
    (net (code "26") (name "/Iout_Bias") (class "Default")
      (node (ref "C51") (pin "2") (pinfunction "2_2") (pintype "passive"))
      (node (ref "D29") (pin "1") (pinfunction "K_1") (pintype "passive"))
      (node (ref "R61") (pin "1") (pinfunction "1_1") (pintype "passive"))
    )
    (net (code "27") (name "/Iout_Bias_1") (class "Default")
      (node (ref "R61") (pin "2") (pinfunction "2_2") (pintype "passive"))
      (node (ref "T20") (pin "1") (pinfunction "VIN_1") (pintype "passive"))
      (node (ref "U12") (pin "6") (pinfunction "VZCR_6") (pintype "passive"))
    )
    (net (code "28") (name "/Iout_HIGH") (class "Default")
      (node (ref "C40") (pin "1") (pinfunction "1_1") (pintype "passive"))
      (node (ref "D24") (pin "1") (pinfunction "K_1") (pintype "passive"))
      (node (ref "R60") (pin "2") (pinfunction "2_2") (pintype "passive"))
    )
    (net (code "29") (name "/Iout_HIGH_1") (class "Default")
      (node (ref "R60") (pin "1") (pinfunction "1_1") (pintype "passive"))
      (node (ref "T16") (pin "1") (pinfunction "VIN_1") (pintype "passive"))
      (node (ref "U12") (pin "7") (pinfunction "OUT_7") (pintype "passive"))
    )
    (net (code "30") (name "/LD1") (class "Default")
      (node (ref "R45") (pin "1") (pinfunction "1_1") (pintype "passive"))
      (node (ref "R47") (pin "1") (pinfunction "1_1") (pintype "passive"))
      (node (ref "T11") (pin "1") (pinfunction "VIN_1") (pintype "passive"))
      (node (ref "U10") (pin "5") (pinfunction "LO_5") (pintype "passive"))
    )
    (net (code "31") (name "/LD2") (class "Default")
      (node (ref "R46") (pin "1") (pinfunction "1_1") (pintype "passive"))
      (node (ref "R48") (pin "1") (pinfunction "1_1") (pintype "passive"))
      (node (ref "T12") (pin "1") (pinfunction "VIN_1") (pintype "passive"))
      (node (ref "U11") (pin "5") (pinfunction "LO_5") (pintype "passive"))
    )
    (net (code "32") (name "/PWM1(TIM1_CH2N_PB14)") (class "Default")
      (node (ref "R62") (pin "2") (pinfunction "2_2") (pintype "passive"))
    )
    (net (code "33") (name "/PWM2(TIM1_CH3N_PB15)") (class "Default")
      (node (ref "R63") (pin "2") (pinfunction "2_2") (pintype "passive"))
    )
    (net (code "34") (name "/SD1(PC8)") (class "Default")
      (node (ref "R65") (pin "2") (pinfunction "2_2") (pintype "passive"))
    )
    (net (code "35") (name "/SD2(PC9)") (class "Default")
      (node (ref "R66") (pin "2") (pinfunction "2_2") (pintype "passive"))
    )
    (net (code "36") (name "/SW1") (class "Default")
      (node (ref "C30") (pin "1") (pinfunction "1_1") (pintype "passive"))
      (node (ref "C44") (pin "2") (pinfunction "2_2") (pintype "passive"))
      (node (ref "D15") (pin "1") (pinfunction "K_1") (pintype "passive"))
      (node (ref "L1") (pin "1") (pinfunction "1_1") (pintype "passive"))
      (node (ref "Q1") (pin "3") (pinfunction "S_3") (pintype "passive"))
      (node (ref "Q3") (pin "2") (pinfunction "D_2") (pintype "passive"))
      (node (ref "R44") (pin "2") (pinfunction "2_2") (pintype "passive"))
      (node (ref "U10") (pin "6") (pinfunction "VS_6") (pintype "passive"))
    )
    (net (code "37") (name "/SW2") (class "Default")
      (node (ref "C29") (pin "1") (pinfunction "1_1") (pintype "passive"))
      (node (ref "C46") (pin "2") (pinfunction "2_2") (pintype "passive"))
      (node (ref "D11") (pin "2") (pinfunction "A_2") (pintype "passive"))
      (node (ref "L1") (pin "2") (pinfunction "2_2") (pintype "passive"))
      (node (ref "Q2") (pin "3") (pinfunction "S_3") (pintype "passive"))
      (node (ref "Q4") (pin "2") (pinfunction "D_2") (pintype "passive"))
      (node (ref "R43") (pin "2") (pinfunction "2_2") (pintype "passive"))
      (node (ref "U11") (pin "6") (pinfunction "VS_6") (pintype "passive"))
    )
    (net (code "38") (name "2.5V_CAP") (class "Default")
      (node (ref "R8") (pin "1") (pinfunction "1_1") (pintype "passive"))
      (node (ref "R9") (pin "2") (pinfunction "2_2") (pintype "passive"))
      (node (ref "T4") (pin "1") (pinfunction "VIN_1") (pintype "passive"))
      (node (ref "U1") (pin "1") (pinfunction "R_1") (pintype "passive"))
      (node (ref "U1") (pin "2") (pinfunction "K_2") (pintype "passive"))
    )
    (net (code "39") (name "2.5V_VIN") (class "Default")
      (node (ref "R55") (pin "1") (pinfunction "1_1") (pintype "passive"))
      (node (ref "R58") (pin "2") (pinfunction "2_2") (pintype "passive"))
      (node (ref "T26") (pin "1") (pinfunction "VIN_1") (pintype "passive"))
      (node (ref "U16") (pin "1") (pinfunction "R_1") (pintype "passive"))
      (node (ref "U16") (pin "2") (pinfunction "K_2") (pintype "passive"))
    )
    (net (code "40") (name "3.3V_CAP") (class "Default")
      (node (ref "C15") (pin "2") (pinfunction "2_2") (pintype "passive"))
      (node (ref "R49") (pin "2") (pinfunction "2_2") (pintype "passive"))
      (node (ref "U5") (pin "8") (pinfunction "VCC_8") (pintype "passive"))
    )
    (net (code "41") (name "3.3V_VCC") (class "Default")
      (node (ref "C11") (pin "2") (pinfunction "2_2") (pintype "passive"))
      (node (ref "R5") (pin "2") (pinfunction "2_2") (pintype "passive"))
      (node (ref "U2") (pin "8") (pinfunction "VCC_8") (pintype "passive"))
    )
    (net (code "42") (name "3.3V_VIN") (class "Default")
      (node (ref "C13") (pin "2") (pinfunction "2_2") (pintype "passive"))
      (node (ref "R27") (pin "2") (pinfunction "2_2") (pintype "passive"))
      (node (ref "U4") (pin "8") (pinfunction "VCC_8") (pintype "passive"))
    )
    (net (code "43") (name "3.3V_VOUT") (class "Default")
      (node (ref "C52") (pin "2") (pinfunction "2_2") (pintype "passive"))
      (node (ref "R50") (pin "2") (pinfunction "2_2") (pintype "passive"))
      (node (ref "U12") (pin "8") (pinfunction "VCC_8") (pintype "passive"))
    )
    (net (code "44") (name "3V3") (class "Default")
      (node (ref "C48") (pin "1") (pinfunction "1_1") (pintype "passive"))
      (node (ref "C49") (pin "2") (pinfunction "2_2") (pintype "passive"))
      (node (ref "D20") (pin "A") (pinfunction "A_A") (pintype "passive"))
      (node (ref "R27") (pin "1") (pinfunction "1_1") (pintype "passive"))
      (node (ref "R49") (pin "1") (pinfunction "1_1") (pintype "passive"))
      (node (ref "R5") (pin "1") (pinfunction "1_1") (pintype "passive"))
      (node (ref "R50") (pin "1") (pinfunction "1_1") (pintype "passive"))
      (node (ref "T3") (pin "1") (pinfunction "VIN_1") (pintype "passive"))
      (node (ref "U8") (pin "2") (pinfunction "VOUT_2") (pintype "passive"))
      (node (ref "U8") (pin "4") (pinfunction "VOUT_4") (pintype "passive"))
    )
    (net (code "45") (name "5V") (class "Default")
      (node (ref "D34") (pin "1") (pinfunction "K_1") (pintype "passive"))
      (node (ref "R13") (pin "1") (pinfunction "1_1") (pintype "passive"))
      (node (ref "R51") (pin "1") (pinfunction "1_1") (pintype "passive"))
      (node (ref "R55") (pin "2") (pinfunction "2_2") (pintype "passive"))
      (node (ref "R8") (pin "2") (pinfunction "2_2") (pintype "passive"))
      (node (ref "T2") (pin "1") (pinfunction "VIN_1") (pintype "passive"))
      (node (ref "U8") (pin "3") (pinfunction "VIN_3") (pintype "passive"))
    )
    (net (code "46") (name "5V_CAP") (class "Default")
      (node (ref "C12") (pin "1") (pinfunction "1_1") (pintype "passive"))
      (node (ref "R13") (pin "2") (pinfunction "2_2") (pintype "passive"))
      (node (ref "U3") (pin "5") (pinfunction "V+_5") (pintype "passive"))
    )
    (net (code "47") (name "5V_VIN") (class "Default")
      (node (ref "C19") (pin "2") (pinfunction "2_2") (pintype "passive"))
      (node (ref "R51") (pin "2") (pinfunction "2_2") (pintype "passive"))
      (node (ref "U6") (pin "5") (pinfunction "V+_5") (pintype "passive"))
    )
    (net (code "48") (name "12V") (class "Default")
      (node (ref "C39") (pin "1") (pinfunction "1_1") (pintype "passive"))
      (node (ref "C43") (pin "2") (pinfunction "2_2") (pintype "passive"))
      (node (ref "C45") (pin "2") (pinfunction "2_2") (pintype "passive"))
      (node (ref "D25") (pin "2") (pinfunction "A_2") (pintype "passive"))
      (node (ref "D26") (pin "2") (pinfunction "A_2") (pintype "passive"))
      (node (ref "T1") (pin "1") (pinfunction "VIN_1") (pintype "passive"))
      (node (ref "U10") (pin "1") (pinfunction "VCC_1") (pintype "passive"))
      (node (ref "U11") (pin "1") (pinfunction "VCC_1") (pintype "passive"))
      (node (ref "U9") (pin "1") (pinfunction "OUT_1") (pintype "passive"))
    )
    (net (code "49") (name "24V_VCC") (class "Default")
      (node (ref "J1") (pin "1") (pinfunction "VCC_1") (pintype "passive"))
      (node (ref "R1") (pin "2") (pinfunction "2_2") (pintype "passive"))
      (node (ref "R59") (pin "2") (pinfunction "2_2") (pintype "passive"))
      (node (ref "U2") (pin "1") (pinfunction "IP+_1") (pintype "passive"))
      (node (ref "U2") (pin "2") (pinfunction "IP+_2") (pintype "passive"))
    )
    (net (code "50") (name "24V_VIN") (class "Default")
      (node (ref "C50") (pin "1") (pinfunction "1_1") (pintype "passive"))
      (node (ref "D38") (pin "1") (pinfunction "K_1") (pintype "passive"))
      (node (ref "D38") (pin "2") (pinfunction "A_2") (pintype "passive"))
      (node (ref "D39") (pin "1") (pinfunction "K_1") (pintype "passive"))
      (node (ref "D39") (pin "2") (pinfunction "A_2") (pintype "passive"))
      (node (ref "F4") (pin "2") (pintype "passive"))
      (node (ref "R28") (pin "2") (pinfunction "2_2") (pintype "passive"))
      (node (ref "R59") (pin "1") (pinfunction "1_1") (pintype "passive"))
      (node (ref "R67") (pin "1") (pinfunction "1_1") (pintype "passive"))
      (node (ref "U12") (pin "1") (pinfunction "IP+_1") (pintype "passive"))
      (node (ref "U12") (pin "2") (pinfunction "IP+_2") (pintype "passive"))
      (node (ref "U2") (pin "3") (pinfunction "IP-_3") (pintype "passive"))
      (node (ref "U2") (pin "4") (pinfunction "IP-_4") (pintype "passive"))
      (node (ref "U4") (pin "1") (pinfunction "IP+_1") (pintype "passive"))
      (node (ref "U4") (pin "2") (pinfunction "IP+_2") (pintype "passive"))
      (node (ref "U9") (pin "3") (pinfunction "IN_3") (pintype "passive"))
    )
    (net (code "51") (name "24V_VOUT") (class "Default")
      (node (ref "C22") (pin "1") (pinfunction "1_1") (pintype "passive"))
      (node (ref "D22") (pin "A") (pinfunction "A_A") (pintype "passive"))
      (node (ref "J3") (pin "1") (pinfunction "VCC_1") (pintype "passive"))
      (node (ref "R3") (pin "2") (pinfunction "2_2") (pintype "passive"))
      (node (ref "R67") (pin "2") (pinfunction "2_2") (pintype "passive"))
      (node (ref "U12") (pin "3") (pinfunction "IP-_3") (pintype "passive"))
      (node (ref "U12") (pin "4") (pinfunction "IP-_4") (pintype "passive"))
    )
    (net (code "52") (name "CAP") (class "Default")
      (node (ref "J2") (pin "1") (pinfunction "VCC_1") (pintype "passive"))
      (node (ref "R29") (pin "1") (pinfunction "1_1") (pintype "passive"))
      (node (ref "R6") (pin "2") (pinfunction "2_2") (pintype "passive"))
      (node (ref "U5") (pin "3") (pinfunction "IP-_3") (pintype "passive"))
      (node (ref "U5") (pin "4") (pinfunction "IP-_4") (pintype "passive"))
    )
    (net (code "53") (name "CAP_GND") (class "Default")
      (node (ref "J2") (pin "2") (pinfunction "GND_2") (pintype "passive"))
      (node (ref "NT1") (pin "1") (pinfunction "1_1") (pintype "passive"))
      (node (ref "R35") (pin "1") (pinfunction "1_1") (pintype "passive"))
    )
    (net (code "54") (name "GND") (class "Default")
      (node (ref "C1") (pin "1") (pinfunction "1_1") (pintype "passive"))
      (node (ref "C10") (pin "1") (pinfunction "1_1") (pintype "passive"))
      (node (ref "C11") (pin "1") (pinfunction "1_1") (pintype "passive"))
      (node (ref "C12") (pin "2") (pinfunction "2_2") (pintype "passive"))
      (node (ref "C13") (pin "1") (pinfunction "1_1") (pintype "passive"))
      (node (ref "C14") (pin "1") (pinfunction "1_1") (pintype "passive"))
      (node (ref "C15") (pin "1") (pinfunction "1_1") (pintype "passive"))
      (node (ref "C19") (pin "1") (pinfunction "1_1") (pintype "passive"))
      (node (ref "C2") (pin "1") (pinfunction "1_1") (pintype "passive"))
      (node (ref "C35") (pin "1") (pinfunction "1_1") (pintype "passive"))
      (node (ref "C36") (pin "1") (pinfunction "1_1") (pintype "passive"))
      (node (ref "C38") (pin "2") (pinfunction "2_2") (pintype "passive"))
      (node (ref "C4") (pin "2") (pinfunction "2_2") (pintype "passive"))
      (node (ref "C40") (pin "2") (pinfunction "2_2") (pintype "passive"))
      (node (ref "C43") (pin "1") (pinfunction "1_1") (pintype "passive"))
      (node (ref "C45") (pin "1") (pinfunction "1_1") (pintype "passive"))
      (node (ref "C48") (pin "2") (pinfunction "2_2") (pintype "passive"))
      (node (ref "C49") (pin "1") (pinfunction "1_1") (pintype "passive"))
      (node (ref "C5") (pin "1") (pinfunction "1_1") (pintype "passive"))
      (node (ref "C50") (pin "2") (pinfunction "2_2") (pintype "passive"))
      (node (ref "C51") (pin "1") (pinfunction "1_1") (pintype "passive"))
      (node (ref "C52") (pin "1") (pinfunction "1_1") (pintype "passive"))
      (node (ref "C6") (pin "2") (pinfunction "2_2") (pintype "passive"))
      (node (ref "C67") (pin "1") (pinfunction "1_1") (pintype "passive"))
      (node (ref "C7") (pin "2") (pinfunction "2_2") (pintype "passive"))
      (node (ref "C8") (pin "2") (pinfunction "2_2") (pintype "passive"))
      (node (ref "C9") (pin "1") (pinfunction "1_1") (pintype "passive"))
      (node (ref "D1") (pin "2") (pinfunction "A_2") (pintype "passive"))
      (node (ref "D10") (pin "2") (pinfunction "A_2") (pintype "passive"))
      (node (ref "D12") (pin "2") (pinfunction "A_2") (pintype "passive"))
      (node (ref "D18") (pin "2") (pinfunction "A_2") (pintype "passive"))
      (node (ref "D2") (pin "2") (pinfunction "A_2") (pintype "passive"))
      (node (ref "D21") (pin "2") (pinfunction "A_2") (pintype "passive"))
      (node (ref "D24") (pin "2") (pinfunction "A_2") (pintype "passive"))
      (node (ref "D28") (pin "2") (pinfunction "A_2") (pintype "passive"))
      (node (ref "D29") (pin "2") (pinfunction "A_2") (pintype "passive"))
      (node (ref "D3") (pin "2") (pinfunction "A_2") (pintype "passive"))
      (node (ref "D30") (pin "2") (pinfunction "A_2") (pintype "passive"))
      (node (ref "D31") (pin "2") (pinfunction "A_2") (pintype "passive"))
      (node (ref "D4") (pin "2") (pinfunction "A_2") (pintype "passive"))
      (node (ref "D5") (pin "2") (pinfunction "A_2") (pintype "passive"))
      (node (ref "D6") (pin "2") (pinfunction "A_2") (pintype "passive"))
      (node (ref "D7") (pin "2") (pinfunction "A_2") (pintype "passive"))
      (node (ref "D8") (pin "2") (pinfunction "A_2") (pintype "passive"))
      (node (ref "D9") (pin "2") (pinfunction "A_2") (pintype "passive"))
      (node (ref "R100") (pin "1") (pinfunction "1_1") (pintype "passive"))
      (node (ref "R15") (pin "2") (pinfunction "2_2") (pintype "passive"))
      (node (ref "R2") (pin "1") (pinfunction "1_1") (pintype "passive"))
      (node (ref "R4") (pin "1") (pinfunction "1_1") (pintype "passive"))
      (node (ref "R53") (pin "1") (pinfunction "1_1") (pintype "passive"))
      (node (ref "R57") (pin "2") (pinfunction "2_2") (pintype "passive"))
      (node (ref "R7") (pin "1") (pinfunction "1_1") (pintype "passive"))
      (node (ref "R71") (pin "1") (pinfunction "1_1") (pintype "passive"))
      (node (ref "R72") (pin "2") (pinfunction "2_2") (pintype "passive"))
      (node (ref "R74") (pin "1") (pinfunction "1_1") (pintype "passive"))
      (node (ref "R79") (pin "1") (pinfunction "1_1") (pintype "passive"))
      (node (ref "R85") (pin "1") (pinfunction "1_1") (pintype "passive"))
      (node (ref "T43") (pin "1") (pinfunction "VIN_1") (pintype "passive"))
      (node (ref "U1") (pin "3") (pinfunction "A_3") (pintype "passive"))
      (node (ref "U12") (pin "5") (pinfunction "GND_5") (pintype "passive"))
      (node (ref "U16") (pin "3") (pinfunction "A_3") (pintype "passive"))
      (node (ref "U2") (pin "5") (pinfunction "GND_5") (pintype "passive"))
      (node (ref "U3") (pin "2") (pinfunction "V-_2") (pintype "passive"))
      (node (ref "U4") (pin "5") (pinfunction "GND_5") (pintype "passive"))
      (node (ref "U5") (pin "5") (pinfunction "GND_5") (pintype "passive"))
      (node (ref "U6") (pin "2") (pinfunction "V-_2") (pintype "passive"))
      (node (ref "U7") (pin "2") (pinfunction "GND_2") (pintype "passive"))
      (node (ref "U8") (pin "1") (pinfunction "GND/ADJ_1") (pintype "passive"))
      (node (ref "U9") (pin "2") (pinfunction "GND_2") (pintype "passive"))
    )
    (net (code "55") (name "Net-(C3-Pad2)") (class "Default")
      (node (ref "C3") (pin "2") (pinfunction "2_2") (pintype "passive"))
      (node (ref "C8") (pin "1") (pinfunction "1_1") (pintype "passive"))
      (node (ref "R10") (pin "2") (pinfunction "2_2") (pintype "passive"))
      (node (ref "R15") (pin "1") (pinfunction "1_1") (pintype "passive"))
      (node (ref "R9") (pin "1") (pinfunction "1_1") (pintype "passive"))
    )
    (net (code "56") (name "Net-(C16-Pad1)") (class "Default")
      (node (ref "C16") (pin "1") (pinfunction "1_1") (pintype "passive"))
      (node (ref "R24") (pin "2") (pinfunction "2_2") (pintype "passive"))
      (node (ref "R25") (pin "1") (pinfunction "1_1") (pintype "passive"))
    )
    (net (code "57") (name "Net-(C16-Pad2)") (class "Default")
      (node (ref "C16") (pin "2") (pinfunction "2_2") (pintype "passive"))
      (node (ref "R22") (pin "2") (pinfunction "2_2") (pintype "passive"))
      (node (ref "R23") (pin "1") (pinfunction "1_1") (pintype "passive"))
    )
    (net (code "58") (name "Net-(C17-Pad1)") (class "Default")
      (node (ref "C17") (pin "1") (pinfunction "1_1") (pintype "passive"))
      (node (ref "R26") (pin "1") (pinfunction "1_1") (pintype "passive"))
      (node (ref "R52") (pin "1") (pinfunction "1_1") (pintype "passive"))
      (node (ref "U3") (pin "4") (pintype "passive"))
    )
    (net (code "59") (name "Net-(C18-Pad2)") (class "Default")
      (node (ref "C18") (pin "2") (pinfunction "2_2") (pintype "passive"))
      (node (ref "C38") (pin "1") (pinfunction "1_1") (pintype "passive"))
      (node (ref "R58") (pin "1") (pinfunction "1_1") (pintype "passive"))
      (node (ref "R69") (pin "2") (pinfunction "2_2") (pintype "passive"))
      (node (ref "R72") (pin "1") (pinfunction "1_1") (pintype "passive"))
    )
    (net (code "60") (name "Net-(C28-Pad1)") (class "Default")
      (node (ref "C28") (pin "1") (pinfunction "1_1") (pintype "passive"))
      (node (ref "R36") (pin "2") (pinfunction "2_2") (pintype "passive"))
      (node (ref "R37") (pin "1") (pinfunction "1_1") (pintype "passive"))
    )
    (net (code "61") (name "Net-(C28-Pad2)") (class "Default")
      (node (ref "C28") (pin "2") (pinfunction "2_2") (pintype "passive"))
      (node (ref "R30") (pin "2") (pinfunction "2_2") (pintype "passive"))
      (node (ref "R31") (pin "1") (pinfunction "1_1") (pintype "passive"))
    )
    (net (code "62") (name "Net-(C29-Pad2)") (class "Default")
      (node (ref "C29") (pin "2") (pinfunction "2_2") (pintype "passive"))
      (node (ref "R32") (pin "1") (pinfunction "1_1") (pintype "passive"))
    )
    (net (code "63") (name "Net-(C30-Pad2)") (class "Default")
      (node (ref "C30") (pin "2") (pinfunction "2_2") (pintype "passive"))
      (node (ref "R33") (pin "1") (pinfunction "1_1") (pintype "passive"))
    )
    (net (code "64") (name "Net-(C31-Pad1)") (class "Default")
      (node (ref "C31") (pin "1") (pinfunction "1_1") (pintype "passive"))
      (node (ref "R42") (pin "1") (pinfunction "1_1") (pintype "passive"))
      (node (ref "R70") (pin "1") (pinfunction "1_1") (pintype "passive"))
      (node (ref "U6") (pin "4") (pintype "passive"))
    )
    (net (code "65") (name "Net-(C32-Pad2)") (class "Default")
      (node (ref "C32") (pin "2") (pinfunction "2_2") (pintype "passive"))
      (node (ref "R44") (pin "1") (pinfunction "1_1") (pintype "passive"))
    )
    (net (code "66") (name "Net-(C33-Pad2)") (class "Default")
      (node (ref "C33") (pin "2") (pinfunction "2_2") (pintype "passive"))
      (node (ref "R43") (pin "1") (pinfunction "1_1") (pintype "passive"))
    )
    (net (code "67") (name "Net-(C39-Pad2)") (class "Default")
      (node (ref "C39") (pin "2") (pinfunction "2_2") (pintype "passive"))
      (node (ref "R74") (pin "2") (pinfunction "2_2") (pintype "passive"))
    )
    (net (code "68") (name "Net-(D11-K)") (class "Default")
      (node (ref "C26") (pin "2") (pinfunction "2_2") (pintype "passive"))
      (node (ref "C27") (pin "2") (pinfunction "2_2") (pintype "passive"))
      (node (ref "C53") (pin "1") (pinfunction "1_1") (pintype "passive"))
      (node (ref "C54") (pin "1") (pinfunction "1_1") (pintype "passive"))
      (node (ref "D11") (pin "1") (pinfunction "K_1") (pintype "passive"))
      (node (ref "Q2") (pin "2") (pinfunction "D_2") (pintype "passive"))
      (node (ref "R29") (pin "2") (pinfunction "2_2") (pintype "passive"))
      (node (ref "R32") (pin "2") (pinfunction "2_2") (pintype "passive"))
      (node (ref "U5") (pin "1") (pinfunction "IP+_1") (pintype "passive"))
      (node (ref "U5") (pin "2") (pinfunction "IP+_2") (pintype "passive"))
    )
    (net (code "69") (name "Net-(D13-A)") (class "Default")
      (node (ref "D13") (pin "2") (pinfunction "A_2") (pintype "passive"))
      (node (ref "Q1") (pin "1") (pinfunction "G_1") (pintype "passive"))
      (node (ref "R38") (pin "2") (pinfunction "2_2") (pintype "passive"))
    )
    (net (code "70") (name "Net-(D13-K)") (class "Default")
      (node (ref "D13") (pin "1") (pinfunction "K_1") (pintype "passive"))
      (node (ref "R40") (pin "2") (pinfunction "2_2") (pintype "passive"))
    )
    (net (code "71") (name "Net-(D14-A)") (class "Default")
      (node (ref "D14") (pin "2") (pinfunction "A_2") (pintype "passive"))
      (node (ref "Q2") (pin "1") (pinfunction "G_1") (pintype "passive"))
      (node (ref "R39") (pin "2") (pinfunction "2_2") (pintype "passive"))
    )
    (net (code "72") (name "Net-(D14-K)") (class "Default")
      (node (ref "D14") (pin "1") (pinfunction "K_1") (pintype "passive"))
      (node (ref "R41") (pin "2") (pinfunction "2_2") (pintype "passive"))
    )
    (net (code "73") (name "Net-(D16-A)") (class "Default")
      (node (ref "D16") (pin "2") (pinfunction "A_2") (pintype "passive"))
      (node (ref "Q3") (pin "1") (pinfunction "G_1") (pintype "passive"))
      (node (ref "R45") (pin "2") (pinfunction "2_2") (pintype "passive"))
    )
    (net (code "74") (name "Net-(D16-K)") (class "Default")
      (node (ref "D16") (pin "1") (pinfunction "K_1") (pintype "passive"))
      (node (ref "R47") (pin "2") (pinfunction "2_2") (pintype "passive"))
    )
    (net (code "75") (name "Net-(D17-A)") (class "Default")
      (node (ref "D17") (pin "2") (pinfunction "A_2") (pintype "passive"))
      (node (ref "Q4") (pin "1") (pinfunction "G_1") (pintype "passive"))
      (node (ref "R46") (pin "2") (pinfunction "2_2") (pintype "passive"))
    )
    (net (code "76") (name "Net-(D17-K)") (class "Default")
      (node (ref "D17") (pin "1") (pinfunction "K_1") (pintype "passive"))
      (node (ref "R48") (pin "2") (pinfunction "2_2") (pintype "passive"))
    )
    (net (code "77") (name "Net-(D20-PadK)") (class "Default")
      (node (ref "D20") (pin "K") (pinfunction "K_K") (pintype "passive"))
      (node (ref "R53") (pin "2") (pinfunction "2_2") (pintype "passive"))
    )
    (net (code "78") (name "Net-(D21-K)") (class "Default")
      (node (ref "C37") (pin "2") (pinfunction "2_2") (pintype "passive"))
      (node (ref "D21") (pin "1") (pinfunction "K_1") (pintype "passive"))
      (node (ref "L2") (pin "1") (pinfunction "1_1") (pintype "passive"))
      (node (ref "U7") (pin "6") (pinfunction "SW_6") (pintype "passive"))
    )
    (net (code "79") (name "Net-(D22-PadK)") (class "Default")
      (node (ref "D22") (pin "K") (pinfunction "K_K") (pintype "passive"))
      (node (ref "R54") (pin "2") (pinfunction "2_2") (pintype "passive"))
    )
    (net (code "80") (name "Net-(D25-K)") (class "Default")
      (node (ref "C44") (pin "1") (pinfunction "1_1") (pintype "passive"))
      (node (ref "D25") (pin "1") (pinfunction "K_1") (pintype "passive"))
      (node (ref "U10") (pin "8") (pinfunction "VB_8") (pintype "passive"))
    )
    (net (code "81") (name "Net-(D26-K)") (class "Default")
      (node (ref "C46") (pin "1") (pinfunction "1_1") (pintype "passive"))
      (node (ref "D26") (pin "1") (pinfunction "K_1") (pintype "passive"))
      (node (ref "U11") (pin "8") (pinfunction "VB_8") (pintype "passive"))
    )
    (net (code "82") (name "Net-(D33-PadK)") (class "Default")
      (node (ref "D33") (pin "K") (pinfunction "K_K") (pintype "passive"))
      (node (ref "R100") (pin "2") (pinfunction "2_2") (pintype "passive"))
    )
    (net (code "83") (name "Net-(D34-A)") (class "Default")
      (node (ref "C34") (pin "2") (pinfunction "2_2") (pintype "passive"))
      (node (ref "C35") (pin "2") (pinfunction "2_2") (pintype "passive"))
      (node (ref "C36") (pin "2") (pinfunction "2_2") (pintype "passive"))
      (node (ref "D34") (pin "2") (pinfunction "A_2") (pintype "passive"))
      (node (ref "L2") (pin "2") (pinfunction "2_2") (pintype "passive"))
      (node (ref "R86") (pin "2") (pinfunction "2_2") (pintype "passive"))
    )
    (net (code "84") (name "Net-(D40-PadK)") (class "Default")
      (node (ref "D40") (pin "K") (pinfunction "K_K") (pintype "passive"))
      (node (ref "R71") (pin "2") (pinfunction "2_2") (pintype "passive"))
    )
    (net (code "85") (name "Net-(U3-+)") (class "Default")
      (node (ref "C3") (pin "1") (pinfunction "1_1") (pintype "passive"))
      (node (ref "R10") (pin "1") (pinfunction "1_1") (pintype "passive"))
      (node (ref "R23") (pin "2") (pinfunction "2_2") (pintype "passive"))
      (node (ref "U3") (pin "1") (pinfunction "+_1") (pintype "passive"))
    )
    (net (code "86") (name "Net-(U3--)") (class "Default")
      (node (ref "C17") (pin "2") (pinfunction "2_2") (pintype "passive"))
      (node (ref "R25") (pin "2") (pinfunction "2_2") (pintype "passive"))
      (node (ref "R26") (pin "2") (pinfunction "2_2") (pintype "passive"))
      (node (ref "U3") (pin "3") (pinfunction "-_3") (pintype "passive"))
    )
    (net (code "87") (name "Net-(U6-+)") (class "Default")
      (node (ref "C18") (pin "1") (pinfunction "1_1") (pintype "passive"))
      (node (ref "R31") (pin "2") (pinfunction "2_2") (pintype "passive"))
      (node (ref "R69") (pin "1") (pinfunction "1_1") (pintype "passive"))
      (node (ref "U6") (pin "1") (pinfunction "+_1") (pintype "passive"))
    )
    (net (code "88") (name "Net-(U6--)") (class "Default")
      (node (ref "C31") (pin "2") (pinfunction "2_2") (pintype "passive"))
      (node (ref "R37") (pin "2") (pinfunction "2_2") (pintype "passive"))
      (node (ref "R42") (pin "2") (pinfunction "2_2") (pintype "passive"))
      (node (ref "U6") (pin "3") (pinfunction "-_3") (pintype "passive"))
    )
    (net (code "89") (name "Net-(U7-BST)") (class "Default")
      (node (ref "C37") (pin "1") (pinfunction "1_1") (pintype "passive"))
      (node (ref "U7") (pin "1") (pinfunction "BST_1") (pintype "passive"))
    )
    (net (code "90") (name "Net-(U7-EN)") (class "Default")
      (node (ref "R56") (pin "1") (pinfunction "1_1") (pintype "passive"))
      (node (ref "R57") (pin "1") (pinfunction "1_1") (pintype "passive"))
      (node (ref "U7") (pin "4") (pinfunction "EN_4") (pintype "passive"))
    )
    (net (code "91") (name "Net-(U7-FB)") (class "Default")
      (node (ref "C34") (pin "1") (pinfunction "1_1") (pintype "passive"))
      (node (ref "R85") (pin "2") (pinfunction "2_2") (pintype "passive"))
      (node (ref "R86") (pin "1") (pinfunction "1_1") (pintype "passive"))
      (node (ref "U7") (pin "3") (pinfunction "FB_3") (pintype "passive"))
    )
    (net (code "92") (name "Net-(U7-VIN)") (class "Default")
      (node (ref "C67") (pin "2") (pinfunction "2_2") (pintype "passive"))
      (node (ref "F4") (pin "1") (pintype "passive"))
      (node (ref "R56") (pin "2") (pinfunction "2_2") (pintype "passive"))
      (node (ref "U7") (pin "5") (pinfunction "VIN_5") (pintype "passive"))
    )
    (net (code "93") (name "PGND") (class "Default")
      (node (ref "C20") (pin "1") (pinfunction "1_1") (pintype "passive"))
      (node (ref "C21") (pin "1") (pinfunction "1_1") (pintype "passive"))
      (node (ref "C24") (pin "2") (pinfunction "2_2") (pintype "passive"))
      (node (ref "C25") (pin "2") (pinfunction "2_2") (pintype "passive"))
      (node (ref "C26") (pin "1") (pinfunction "1_1") (pintype "passive"))
      (node (ref "C27") (pin "1") (pinfunction "1_1") (pintype "passive"))
      (node (ref "C32") (pin "1") (pinfunction "1_1") (pintype "passive"))
      (node (ref "C33") (pin "1") (pinfunction "1_1") (pintype "passive"))
      (node (ref "C53") (pin "2") (pinfunction "2_2") (pintype "passive"))
      (node (ref "C54") (pin "2") (pinfunction "2_2") (pintype "passive"))
      (node (ref "D15") (pin "2") (pinfunction "A_2") (pintype "passive"))
      (node (ref "NT2") (pin "1") (pinfunction "1_1") (pintype "passive"))
      (node (ref "NT3") (pin "1") (pinfunction "1_1") (pintype "passive"))
      (node (ref "Q3") (pin "3") (pinfunction "S_3") (pintype "passive"))
      (node (ref "Q4") (pin "3") (pinfunction "S_3") (pintype "passive"))
      (node (ref "R34") (pin "1") (pinfunction "1_1") (pintype "passive"))
      (node (ref "R35") (pin "2") (pinfunction "2_2") (pintype "passive"))
      (node (ref "U10") (pin "4") (pinfunction "COM_4") (pintype "passive"))
      (node (ref "U11") (pin "4") (pinfunction "COM_4") (pintype "passive"))
    )
    (net (code "94") (name "SD1") (class "Default")
      (node (ref "D30") (pin "1") (pinfunction "K_1") (pintype "passive"))
      (node (ref "D40") (pin "A") (pinfunction "A_A") (pintype "passive"))
      (node (ref "R65") (pin "1") (pinfunction "1_1") (pintype "passive"))
      (node (ref "T25") (pin "1") (pinfunction "VIN_1") (pintype "passive"))
      (node (ref "U10") (pin "3") (pinfunction "SD#_3") (pintype "passive"))
    )
    (net (code "95") (name "SD2") (class "Default")
      (node (ref "D31") (pin "1") (pinfunction "K_1") (pintype "passive"))
      (node (ref "D33") (pin "A") (pinfunction "A_A") (pintype "passive"))
      (node (ref "R66") (pin "1") (pinfunction "1_1") (pintype "passive"))
      (node (ref "T27") (pin "1") (pinfunction "VIN_1") (pintype "passive"))
      (node (ref "U11") (pin "3") (pinfunction "SD#_3") (pintype "passive"))
    )
    (net (code "96") (name "VGND") (class "Default")
      (node (ref "C22") (pin "2") (pinfunction "2_2") (pintype "passive"))
      (node (ref "J1") (pin "2") (pinfunction "GND_2") (pintype "passive"))
      (node (ref "J3") (pin "2") (pinfunction "GND_2") (pintype "passive"))
      (node (ref "NT4") (pin "1") (pinfunction "1_1") (pintype "passive"))
      (node (ref "R34") (pin "2") (pinfunction "2_2") (pintype "passive"))
      (node (ref "R54") (pin "1") (pinfunction "1_1") (pintype "passive"))
      (node (ref "R79") (pin "2") (pinfunction "2_2") (pintype "passive"))
    )
    (net (code "97") (name "VIN_CAP") (class "Default")
      (node (ref "C20") (pin "2") (pinfunction "2_2") (pintype "passive"))
      (node (ref "C21") (pin "2") (pinfunction "2_2") (pintype "passive"))
      (node (ref "C24") (pin "1") (pinfunction "1_1") (pintype "passive"))
      (node (ref "C25") (pin "1") (pinfunction "1_1") (pintype "passive"))
      (node (ref "Q1") (pin "2") (pinfunction "D_2") (pintype "passive"))
      (node (ref "R28") (pin "1") (pinfunction "1_1") (pintype "passive"))
      (node (ref "R33") (pin "2") (pinfunction "2_2") (pintype "passive"))
      (node (ref "U4") (pin "3") (pinfunction "IP-_3") (pintype "passive"))
      (node (ref "U4") (pin "4") (pinfunction "IP-_4") (pintype "passive"))
    )
  )
)
